# CAN_TO_USART_V2_2.net
KiCad netlist of a schematic drawn in Altium Designer
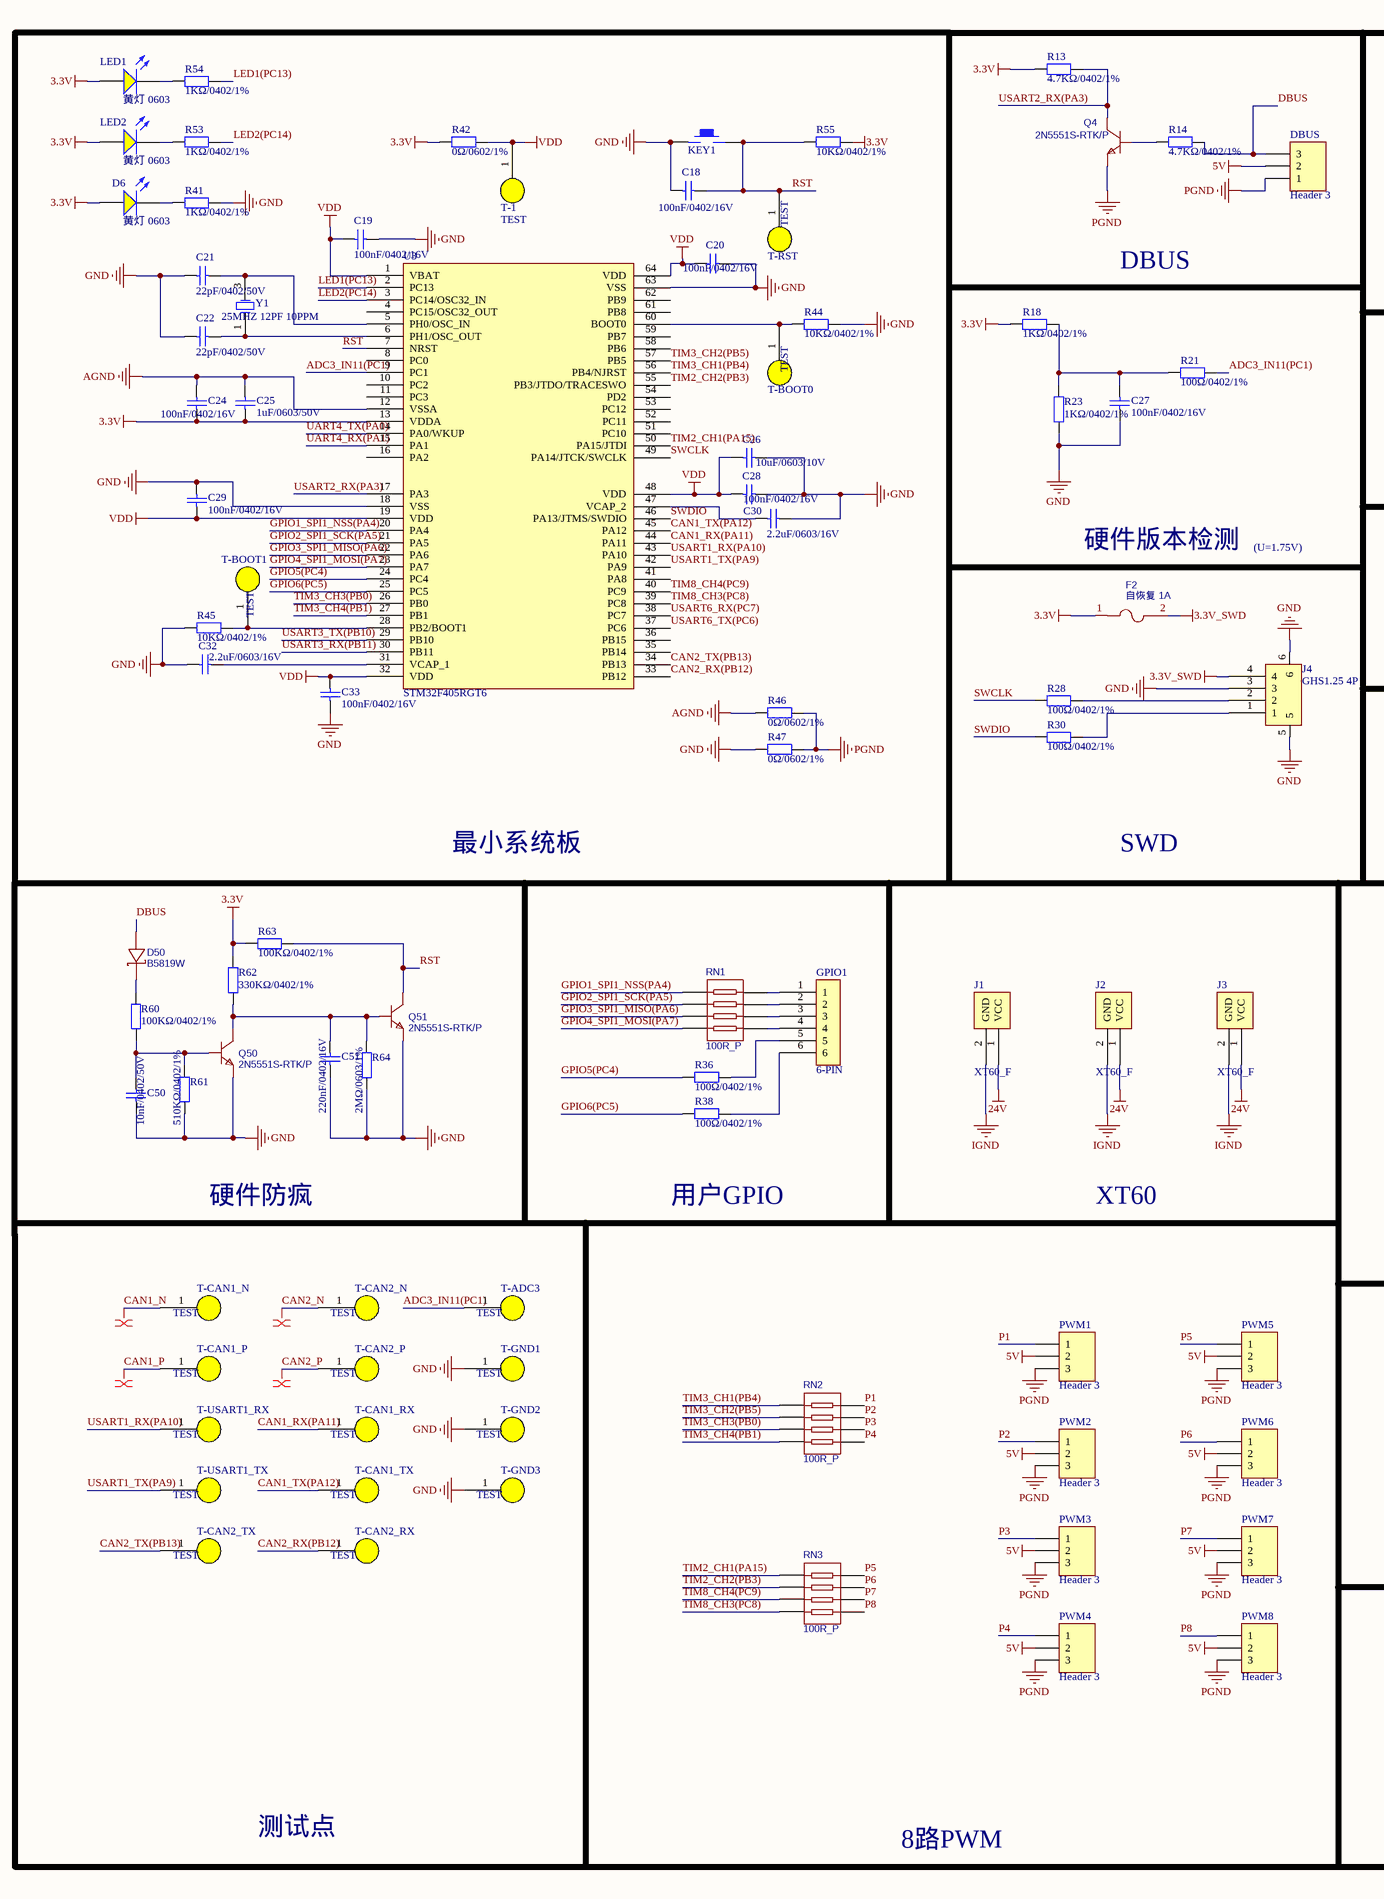
[diagram p0: CAN_TO_USART_V2.2.SchDoc, left]
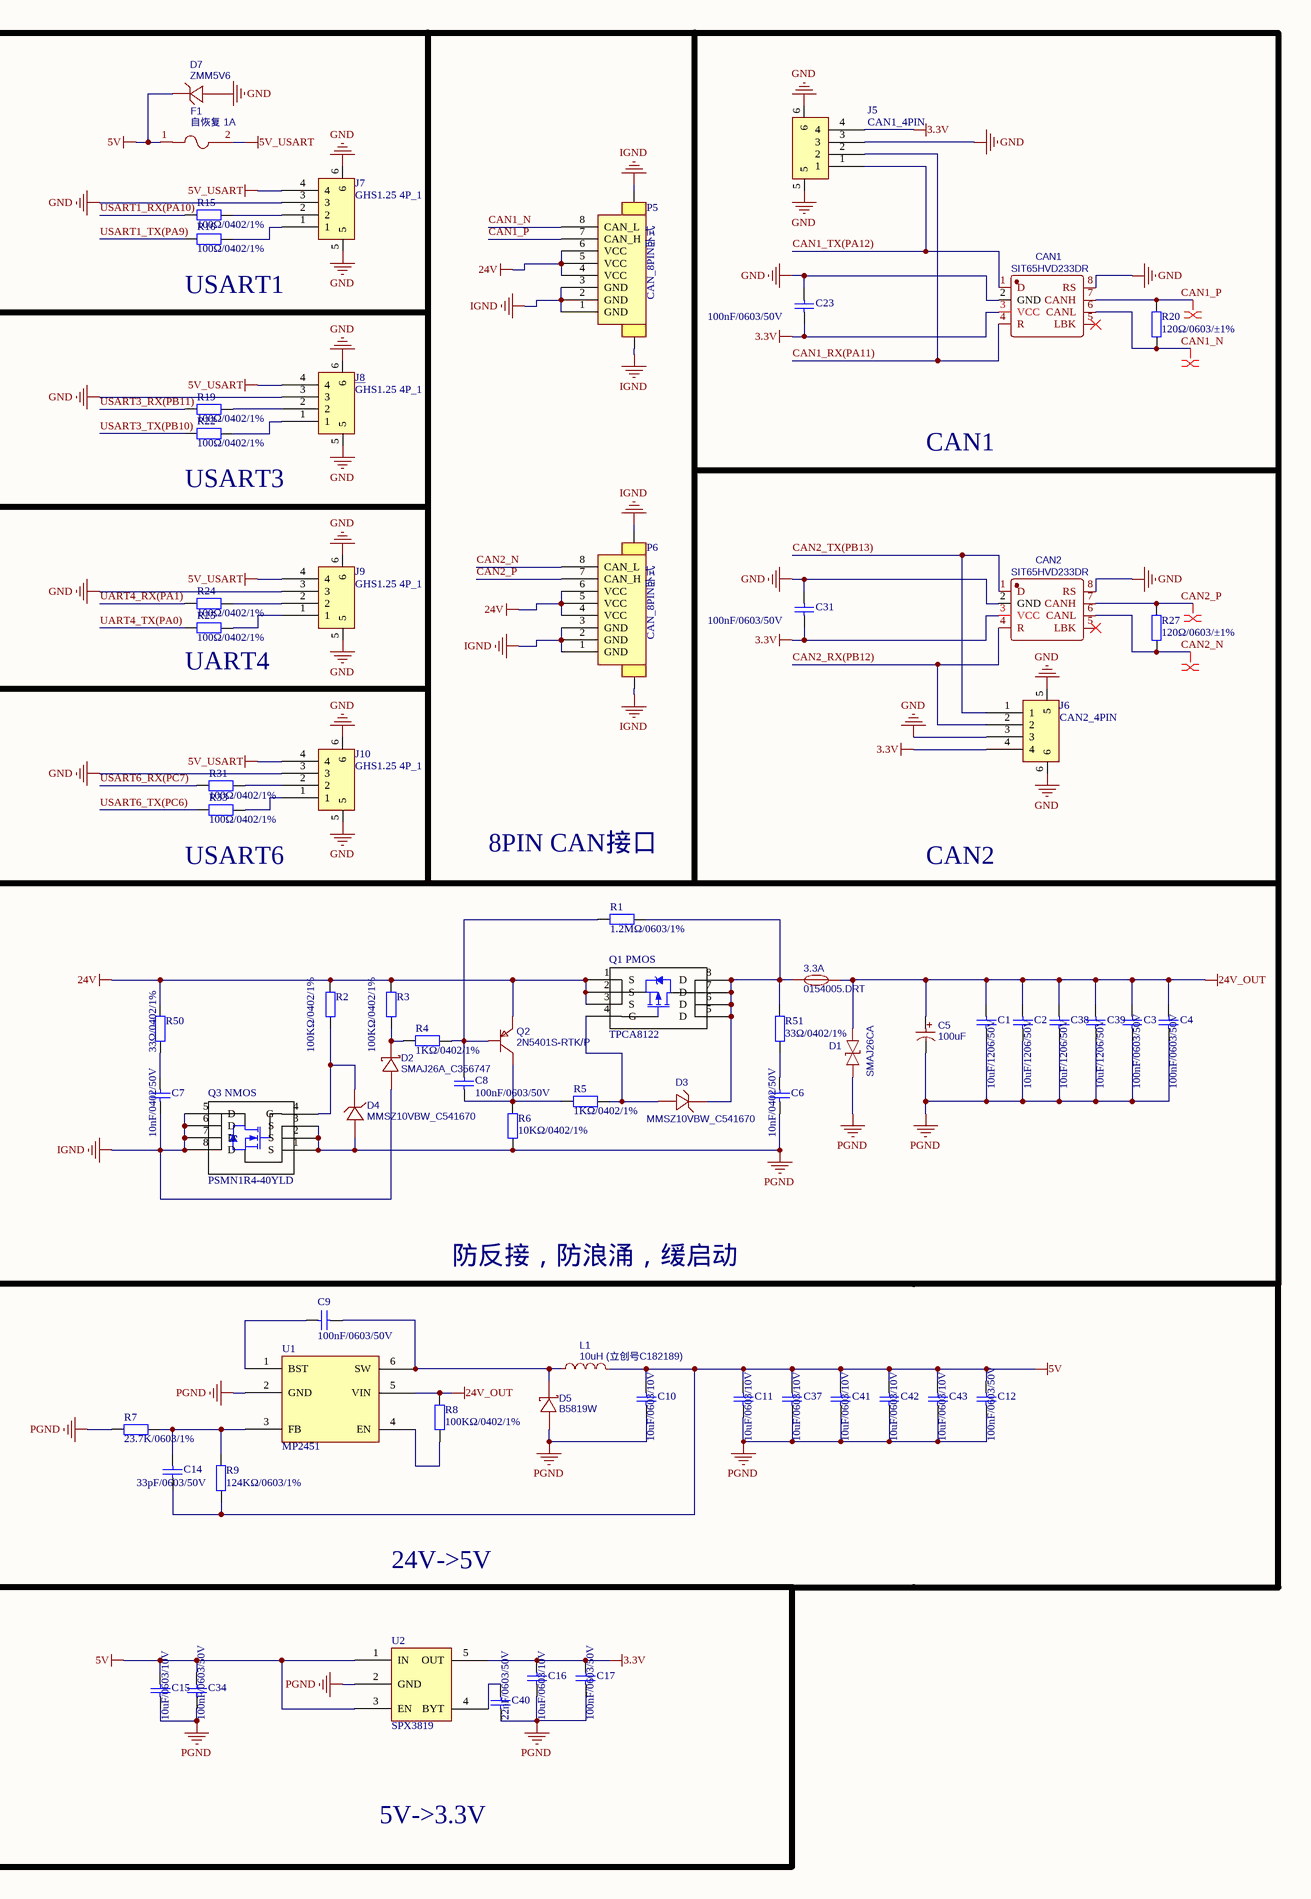
[diagram p1: CAN_TO_USART_V2.2.SchDoc, right]

(export (version "E")
  (design (tool "Eeschema 10.0.6"))
  (components
    (comp (ref "3.3A")
      (value "0154005.DRT")
      (footprint "FUSE 3.3A")
      (fields (field (name "BOM_SUPPLIER PART") "C206917") (field (name "CONTRIBUTOR") "LCSC"))
      (libsource (lib "altium-import") (part "root_0_mirrored_0154005.DRT_"))
    )
    (comp (ref "C1")
      (value "10uF/1206/50V")
      (footprint "1206_C")
      (description "贴片电容")
      (libsource (lib "Miscellaneous Devices LC") (part "1206 10uF (106) 10% 50V"))
    )
    (comp (ref "C2")
      (value "10uF/1206/50V")
      (footprint "1206_C")
      (description "贴片电容")
      (libsource (lib "Miscellaneous Devices LC") (part "1206 10uF (106) 10% 50V"))
    )
    (comp (ref "C3")
      (value "100nF/0603/50V")
      (footprint "0603_C")
      (description "贴片电容")
      (libsource (lib "Miscellaneous Devices LC") (part "0603 100nF (104) 10% 50V"))
    )
    (comp (ref "C4")
      (value "100nF/0603/50V")
      (footprint "0603_C")
      (description "贴片电容")
      (libsource (lib "Miscellaneous Devices LC") (part "0603 100nF (104) 10% 50V"))
    )
    (comp (ref "C5")
      (value "100uF")
      (footprint "100UF E")
      (fields
        (field (name "BOM_MANUFACTURER PART") "50V 100uF 8X12")
        (field (name "BOM_SUPPLIER PART") "C2749")
      )
      (libsource (lib "altium-import") (part "root_3_100uF_"))
    )
    (comp (ref "C6")
      (value "10nF/0402/50V")
      (footprint "0402_C")
      (description "贴片电容")
      (libsource (lib "Miscellaneous Devices LC") (part "0402 10nF (103) 10% 50V"))
    )
    (comp (ref "C7")
      (value "10nF/0402/50V")
      (footprint "0402_C")
      (description "贴片电容")
      (libsource (lib "Miscellaneous Devices LC") (part "0402 10nF (103) 10% 50V"))
    )
    (comp (ref "C8")
      (value "100nF/0603/50V")
      (footprint "0603_C")
      (description "贴片电容")
      (libsource (lib "Miscellaneous Devices LC") (part "0603 100nF (104) 10% 50V"))
    )
    (comp (ref "C9")
      (value "100nF/0603/50V")
      (footprint "0603_C")
      (description "贴片电容")
      (libsource (lib "Miscellaneous Devices LC") (part "0603 100nF (104) 10% 50V"))
    )
    (comp (ref "C10")
      (value "10uF/0603/10V")
      (footprint "0603_C")
      (description "贴片电容")
      (libsource (lib "Miscellaneous Devices LC") (part "0603 10uF (106) 10% 10V"))
    )
    (comp (ref "C11")
      (value "10uF/0603/10V")
      (footprint "0603_C")
      (description "贴片电容")
      (libsource (lib "Miscellaneous Devices LC") (part "0603 10uF (106) 10% 10V"))
    )
    (comp (ref "C12")
      (value "100nF/0603/50V")
      (footprint "0603_C")
      (description "贴片电容")
      (libsource (lib "Miscellaneous Devices LC") (part "0603 100nF (104) 10% 50V"))
    )
    (comp (ref "C14")
      (value "33pF/0603/50V")
      (footprint "0603_C")
      (description "贴片电容")
      (libsource (lib "Miscellaneous Devices LC") (part "0603 33pF (330) 5% 50V"))
    )
    (comp (ref "C15")
      (value "10uF/0603/10V")
      (footprint "0603_C")
      (description "贴片电容")
      (libsource (lib "Miscellaneous Devices LC") (part "0603 10uF (106) 10% 10V"))
    )
    (comp (ref "C16")
      (value "10uF/0603/10V")
      (footprint "0603_C")
      (description "贴片电容")
      (libsource (lib "Miscellaneous Devices LC") (part "0603 10uF (106) 10% 10V"))
    )
    (comp (ref "C17")
      (value "100nF/0603/50V")
      (footprint "0603_C")
      (description "贴片电容")
      (libsource (lib "Miscellaneous Devices LC") (part "0603 100nF (104) 10% 50V"))
    )
    (comp (ref "C18")
      (value "100nF/0402/16V")
      (footprint "0402_C")
      (description "贴片电容")
      (libsource (lib "Miscellaneous Devices LC") (part "0402 100nF (104) 10% 16V"))
    )
    (comp (ref "C19")
      (value "100nF/0402/16V")
      (footprint "0402_C")
      (description "贴片电容")
      (libsource (lib "Miscellaneous Devices LC") (part "0402 100nF (104) 10% 16V"))
    )
    (comp (ref "C20")
      (value "100nF/0402/16V")
      (footprint "0402_C")
      (description "贴片电容")
      (libsource (lib "Miscellaneous Devices LC") (part "0402 100nF (104) 10% 16V"))
    )
    (comp (ref "C21")
      (value "22pF/0402/50V")
      (footprint "0402_C")
      (description "贴片电容")
      (libsource (lib "Miscellaneous Devices LC") (part "0402 22pF (220) 5% 50V"))
    )
    (comp (ref "C22")
      (value "22pF/0402/50V")
      (footprint "0402_C")
      (description "贴片电容")
      (libsource (lib "Miscellaneous Devices LC") (part "0402 22pF (220) 5% 50V"))
    )
    (comp (ref "C23")
      (value "100nF/0603/50V")
      (footprint "0603_C")
      (description "贴片电容")
      (libsource (lib "Miscellaneous Devices LC") (part "0603 100nF (104) 10% 50V"))
    )
    (comp (ref "C24")
      (value "100nF/0402/16V")
      (footprint "0402_C")
      (description "贴片电容")
      (libsource (lib "Miscellaneous Devices LC") (part "0402 100nF (104) 10% 16V"))
    )
    (comp (ref "C25")
      (value "1uF/0603/50V")
      (footprint "0603_C")
      (description "贴片电容")
      (libsource (lib "Miscellaneous Devices LC") (part "0603 1uF (105) 10% 50V"))
    )
    (comp (ref "C26")
      (value "10uF/0603/10V")
      (footprint "0603_C")
      (description "贴片电容")
      (libsource (lib "Miscellaneous Devices LC") (part "0603 10uF (106) 10% 10V"))
    )
    (comp (ref "C27")
      (value "100nF/0402/16V")
      (footprint "0402_C")
      (description "贴片电容")
      (libsource (lib "Miscellaneous Devices LC") (part "0402 100nF (104) 10% 16V"))
    )
    (comp (ref "C28")
      (value "100nF/0402/16V")
      (footprint "0402_C")
      (description "贴片电容")
      (libsource (lib "Miscellaneous Devices LC") (part "0402 100nF (104) 10% 16V"))
    )
    (comp (ref "C29")
      (value "100nF/0402/16V")
      (footprint "0402_C")
      (description "贴片电容")
      (libsource (lib "Miscellaneous Devices LC") (part "0402 100nF (104) 10% 16V"))
    )
    (comp (ref "C30")
      (value "2.2uF/0603/16V")
      (footprint "0603_C")
      (description "贴片电容")
      (libsource (lib "Miscellaneous Devices LC") (part "0603 2.2uF (225) 10% 16V"))
    )
    (comp (ref "C31")
      (value "100nF/0603/50V")
      (footprint "0603_C")
      (description "贴片电容")
      (libsource (lib "Miscellaneous Devices LC") (part "0603 100nF (104) 10% 50V"))
    )
    (comp (ref "C32")
      (value "2.2uF/0603/16V")
      (footprint "0603_C")
      (description "贴片电容")
      (libsource (lib "Miscellaneous Devices LC") (part "0603 2.2uF (225) 10% 16V"))
    )
    (comp (ref "C33")
      (value "100nF/0402/16V")
      (footprint "0402_C")
      (description "贴片电容")
      (libsource (lib "Miscellaneous Devices LC") (part "0402 100nF (104) 10% 16V"))
    )
    (comp (ref "C34")
      (value "100nF/0603/50V")
      (footprint "0603_C")
      (description "贴片电容")
      (libsource (lib "Miscellaneous Devices LC") (part "0603 100nF (104) 10% 50V"))
    )
    (comp (ref "C37")
      (value "10uF/0603/10V")
      (footprint "0603_C")
      (description "贴片电容")
      (libsource (lib "Miscellaneous Devices LC") (part "0603 10uF (106) 10% 10V"))
    )
    (comp (ref "C38")
      (value "10uF/1206/50V")
      (footprint "1206_C")
      (description "贴片电容")
      (libsource (lib "Miscellaneous Devices LC") (part "1206 10uF (106) 10% 50V"))
    )
    (comp (ref "C39")
      (value "10uF/1206/50V")
      (footprint "1206_C")
      (description "贴片电容")
      (libsource (lib "Miscellaneous Devices LC") (part "1206 10uF (106) 10% 50V"))
    )
    (comp (ref "C40")
      (value "22nF/0603/50V")
      (footprint "0603_C")
      (description "贴片电容")
      (libsource (lib "Miscellaneous Devices LC") (part "0603 22nF (223) 10% 50V"))
    )
    (comp (ref "C41")
      (value "10uF/0603/10V")
      (footprint "0603_C")
      (description "贴片电容")
      (libsource (lib "Miscellaneous Devices LC") (part "0603 10uF (106) 10% 10V"))
    )
    (comp (ref "C42")
      (value "10uF/0603/10V")
      (footprint "0603_C")
      (description "贴片电容")
      (libsource (lib "Miscellaneous Devices LC") (part "0603 10uF (106) 10% 10V"))
    )
    (comp (ref "C43")
      (value "10uF/0603/10V")
      (footprint "0603_C")
      (description "贴片电容")
      (libsource (lib "Miscellaneous Devices LC") (part "0603 10uF (106) 10% 10V"))
    )
    (comp (ref "C50")
      (value "10nF/0402/50V")
      (footprint "0402_C")
      (description "贴片电容")
      (libsource (lib "Miscellaneous Devices LC") (part "0402 10nF (103) 10% 50V"))
    )
    (comp (ref "C51")
      (value "220nF/0402/16V")
      (footprint "0402_C")
      (description "贴片电容")
      (libsource (lib "Miscellaneous Devices LC") (part "0402 220nF (224) 10% 16V"))
    )
    (comp (ref "CAN1")
      (value "SIT65HVD233DR")
      (footprint "CAN-MCU")
      (fields (field (name "BOM_SUPPLIER PART") "C496620") (field (name "CONTRIBUTOR") "LCSC"))
      (libsource (lib "altium-import") (part "root_0_SIT65HVD233DR_"))
    )
    (comp (ref "CAN2")
      (value "SIT65HVD233DR")
      (footprint "CAN-MCU")
      (fields (field (name "BOM_SUPPLIER PART") "C496620") (field (name "CONTRIBUTOR") "LCSC"))
      (libsource (lib "altium-import") (part "root_0_SIT65HVD233DR_"))
    )
    (comp (ref "D1")
      (value "SMAJ26CA")
      (footprint "SMAJ26CA")
      (fields (field (name "BOM_SUPPLIER PART") "C353459") (field (name "CONTRIBUTOR") "LCSC"))
      (libsource (lib "altium-import") (part "root_1_SMAJ26CA_C353459_"))
    )
    (comp (ref "D2")
      (value "SMAJ26A_C356747")
      (footprint "SMA_L4.4-W2.8-LS5.4-RD")
      (fields
        (field (name "BOM_SUPPLIER PART") "C356747")
        (field (name "BOM_MANUFACTURER PART") "SMAJ26A")
        (field (name "CONTRIBUTOR") "LCSC")
      )
      (libsource (lib "altium-import") (part "root_3_SMAJ26A_C356747_"))
    )
    (comp (ref "D3")
      (value "MMSZ10VBW_C541670")
      (footprint "SOD-123_L2.7-W1.6-LS3.7-RD")
      (fields
        (field (name "BOM_SUPPLIER PART") "C541670")
        (field (name "BOM_MANUFACTURER PART") "MMSZ10VBW")
        (field (name "CONTRIBUTOR") "LCSC")
      )
      (libsource (lib "altium-import") (part "root_2_MMSZ10VBW_C541670_"))
    )
    (comp (ref "D4")
      (value "MMSZ10VBW_C541670")
      (footprint "SOD-123_L2.7-W1.6-LS3.7-RD")
      (fields
        (field (name "BOM_SUPPLIER PART") "C541670")
        (field (name "BOM_MANUFACTURER PART") "MMSZ10VBW")
        (field (name "CONTRIBUTOR") "LCSC")
      )
      (libsource (lib "altium-import") (part "root_3_MMSZ10VBW_C541670_"))
    )
    (comp (ref "D5")
      (value "B5819W")
      (footprint "SOD-123_L2.8-W1.8-LS3.7-RD")
      (fields (field (name "BOM_SUPPLIER PART") "C64885"))
      (libsource (lib "altium-import") (part "root_3_B5819W_"))
    )
    (comp (ref "D6")
      (value "黄灯 0603")
      (footprint "0603_LED_S1")
      (description "发光二极管")
      (libsource (lib "Miscellaneous Devices LC") (part "0603 黄灯"))
    )
    (comp (ref "D7")
      (value "ZMM5V6")
      (footprint "ZMM5.6V")
      (fields (field (name "BOM_SUPPLIER PART") "C8062"))
      (libsource (lib "altium-import") (part "root_0_ZMM5V6_"))
    )
    (comp (ref "D50")
      (value "B5819W")
      (footprint "SOD-123_L2.8-W1.8-LS3.7-RD")
      (fields (field (name "BOM_SUPPLIER PART") "C64885"))
      (libsource (lib "altium-import") (part "root_1_B5819W_"))
    )
    (comp (ref "DBUS")
      (value "Header 3")
      (footprint "HDR1X3")
      (description "Header, 3-Pin")
      (fields (field (name "PUBLISHER") "Altium Limited"))
      (libsource (lib "Miscellaneous Connectors") (part "Header 3"))
    )
    (comp (ref "F1")
      (value "自恢复 1A")
      (footprint "1A 0805")
      (fields
        (field (name "BOM_MANUFACTURER PART") "ASMD1206-100")
        (field (name "BOM_SUPPLIER PART") "C135340")
        (field (name "CONTRIBUTOR") "LCSC")
      )
      (libsource (lib "altium-import") (part "root_0_ASMD1206-100_"))
    )
    (comp (ref "F2")
      (value "自恢复 1A")
      (footprint "1A 0805")
      (fields
        (field (name "BOM_MANUFACTURER PART") "ASMD1206-100")
        (field (name "BOM_SUPPLIER PART") "C135340")
        (field (name "CONTRIBUTOR") "LCSC")
      )
      (libsource (lib "altium-import") (part "root_0_ASMD1206-100_"))
    )
    (comp (ref "GPIO1") (value "6-PIN") (footprint "6P") (libsource (lib "Chassis_Con") (part "6-PIN")))
    (comp (ref "J1")
      (value "XT60_F")
      (footprint "RobotLab_Common_Used:XT60_F（立式）")
      (libsource (lib "RobotLab_Common_Used") (part "XT60_F"))
    )
    (comp (ref "J2")
      (value "XT60_F")
      (footprint "RobotLab_Common_Used:XT60_F（立式）")
      (libsource (lib "RobotLab_Common_Used") (part "XT60_F"))
    )
    (comp (ref "J3")
      (value "XT60_F")
      (footprint "RobotLab_Common_Used:XT60_F（立式）")
      (libsource (lib "RobotLab_Common_Used") (part "XT60_F"))
    )
    (comp (ref "J4")
      (value "GHS1.25 4P")
      (footprint "RobotLab_Common_Used:SM04B-GHS立式")
      (description "立式")
      (libsource (lib "RobotLab_Common_Used") (part "GHS1.25 4P"))
    )
    (comp (ref "J5")
      (value "CAN1_4PIN")
      (footprint "RobotLab_Common_Used:SM04B-GHS卧式")
      (description "卧式短边")
      (libsource (lib "") (part "GHS1.25 4P_1_1"))
    )
    (comp (ref "J6")
      (value "CAN2_4PIN")
      (footprint "RobotLab_Common_Used:SM04B-GHS卧式")
      (description "卧式短边")
      (libsource (lib "") (part "GHS1.25 4P_1_2"))
    )
    (comp (ref "J7")
      (value "GHS1.25 4P_1")
      (footprint "RobotLab_Common_Used:SM04B-GHS卧式")
      (description "卧式短边")
      (libsource (lib "RobotLab_Common_Used") (part "GHS1.25 4P_1"))
    )
    (comp (ref "J8")
      (value "GHS1.25 4P_1")
      (footprint "RobotLab_Common_Used:SM04B-GHS卧式")
      (description "卧式短边")
      (libsource (lib "RobotLab_Common_Used") (part "GHS1.25 4P_1"))
    )
    (comp (ref "J9")
      (value "GHS1.25 4P_1")
      (footprint "RobotLab_Common_Used:SM04B-GHS卧式")
      (description "卧式短边")
      (libsource (lib "RobotLab_Common_Used") (part "GHS1.25 4P_1"))
    )
    (comp (ref "J10")
      (value "GHS1.25 4P_1")
      (footprint "RobotLab_Common_Used:SM04B-GHS卧式")
      (description "卧式短边")
      (libsource (lib "RobotLab_Common_Used") (part "GHS1.25 4P_1"))
    )
    (comp (ref "KEY1") (value "KEY_M") (footprint "KEY") (libsource (lib "MiniSTM32 V3.0封装库") (part "KEY_M")))
    (comp (ref "L1")
      (value "10uH (立创号C182189)")
      (footprint "10UH 1A")
      (fields
        (field (name "BOM_SUPPLIER PART") "C182189")
        (field (name "BOM_MANUFACTURER PART") "SLW5040S100MST")
        (field (name "CONTRIBUTOR") "LCSC")
      )
      (libsource (lib "altium-import") (part "root_0_10uH_"))
    )
    (comp (ref "LED1")
      (value "黄灯 0603")
      (footprint "0603_LED_S1")
      (description "发光二极管")
      (libsource (lib "Miscellaneous Devices LC") (part "0603 黄灯"))
    )
    (comp (ref "LED2")
      (value "黄灯 0603")
      (footprint "0603_LED_S1")
      (description "发光二极管")
      (libsource (lib "Miscellaneous Devices LC") (part "0603 黄灯"))
    )
    (comp (ref "P5")
      (value "CAN_8PIN卧式")
      (footprint "RobotLab_Common_Used:8Pin")
      (description "卧式")
      (libsource (lib "RobotLab_Common_Used") (part "CAN_8PIN"))
    )
    (comp (ref "P6")
      (value "CAN_8PIN卧式")
      (footprint "RobotLab_Common_Used:8Pin")
      (description "卧式")
      (libsource (lib "RobotLab_Common_Used") (part "CAN_8PIN"))
    )
    (comp (ref "PWM1")
      (value "Header 3")
      (footprint "HDR1X3")
      (description "Header, 3-Pin")
      (fields (field (name "PUBLISHER") "Altium Limited"))
      (libsource (lib "") (part "Header 3_1"))
    )
    (comp (ref "PWM2")
      (value "Header 3")
      (footprint "HDR1X3")
      (description "Header, 3-Pin")
      (fields (field (name "PUBLISHER") "Altium Limited"))
      (libsource (lib "") (part "Header 3_1"))
    )
    (comp (ref "PWM3")
      (value "Header 3")
      (footprint "HDR1X3")
      (description "Header, 3-Pin")
      (fields (field (name "PUBLISHER") "Altium Limited"))
      (libsource (lib "") (part "Header 3_1"))
    )
    (comp (ref "PWM4")
      (value "Header 3")
      (footprint "HDR1X3")
      (description "Header, 3-Pin")
      (fields (field (name "PUBLISHER") "Altium Limited"))
      (libsource (lib "") (part "Header 3_1"))
    )
    (comp (ref "PWM5")
      (value "Header 3")
      (footprint "HDR1X3")
      (description "Header, 3-Pin")
      (fields (field (name "PUBLISHER") "Altium Limited"))
      (libsource (lib "") (part "Header 3_1"))
    )
    (comp (ref "PWM6")
      (value "Header 3")
      (footprint "HDR1X3")
      (description "Header, 3-Pin")
      (fields (field (name "PUBLISHER") "Altium Limited"))
      (libsource (lib "") (part "Header 3_1"))
    )
    (comp (ref "PWM7")
      (value "Header 3")
      (footprint "HDR1X3")
      (description "Header, 3-Pin")
      (fields (field (name "PUBLISHER") "Altium Limited"))
      (libsource (lib "") (part "Header 3_1"))
    )
    (comp (ref "PWM8")
      (value "Header 3")
      (footprint "HDR1X3")
      (description "Header, 3-Pin")
      (fields (field (name "PUBLISHER") "Altium Limited"))
      (libsource (lib "") (part "Header 3_1"))
    )
    (comp (ref "Q1 PMOS")
      (value "TPCA8122")
      (footprint "PMOS TCPA8122")
      (fields (field (name "PUBLISHER") "Altium Limited"))
      (libsource (lib "CAN_TO_USART") (part "PMOS 8PIN"))
    )
    (comp (ref "Q2")
      (value "2N5401S-RTK/P")
      (footprint "SOT-23-3_L2.9-W1.6-P1.90-LS2.8-TR-CW")
      (fields (field (name "BOM_SUPPLIER PART") "C147293") (field (name "CONTRIBUTOR") "LCSC"))
      (libsource (lib "altium-import") (part "root_2_mirrored_2N5401S-RTK/P_"))
    )
    (comp (ref "Q3 NMOS")
      (value "PSMN1R4-40YLD")
      (footprint "NMOS PSMN1R5-30")
      (fields (field (name "PUBLISHER") "Altium Limited"))
      (libsource (lib "CAN_TO_USART") (part "NMOS 8PIN"))
    )
    (comp (ref "Q4")
      (value "2N5551S-RTK/P")
      (footprint "2N5551")
      (fields (field (name "BOM_SUPPLIER PART") "C112669") (field (name "CONTRIBUTOR") "LCSC"))
      (libsource (lib "altium-import") (part "root_0_mirrored_2N5551S-RTK/P_"))
    )
    (comp (ref "Q50")
      (value "2N5551S-RTK/P")
      (footprint "2N5551")
      (fields (field (name "BOM_SUPPLIER PART") "C112669") (field (name "CONTRIBUTOR") "LCSC"))
      (libsource (lib "altium-import") (part "root_0_2N5551S-RTK/P_"))
    )
    (comp (ref "Q51")
      (value "2N5551S-RTK/P")
      (footprint "2N5551")
      (fields (field (name "BOM_SUPPLIER PART") "C112669") (field (name "CONTRIBUTOR") "LCSC"))
      (libsource (lib "altium-import") (part "root_0_2N5551S-RTK/P_"))
    )
    (comp (ref "R1")
      (value "1.2MΩ/0603/1%")
      (footprint "0603_R")
      (description "贴片电阻")
      (libsource (lib "Miscellaneous Devices LC") (part "0603 1.2MΩ (1204) 1%"))
    )
    (comp (ref "R2")
      (value "100KΩ/0402/1%")
      (footprint "0402_R")
      (description "贴片电阻")
      (libsource (lib "Miscellaneous Devices LC") (part "0402 100KΩ (1003) 1%"))
    )
    (comp (ref "R3")
      (value "100KΩ/0402/1%")
      (footprint "0402_R")
      (description "贴片电阻")
      (libsource (lib "Miscellaneous Devices LC") (part "0402 100KΩ (1003) 1%"))
    )
    (comp (ref "R4")
      (value "1KΩ/0402/1%")
      (footprint "0402_R")
      (description "贴片电阻")
      (libsource (lib "Miscellaneous Devices LC") (part "0402 1KΩ (1001) 1%"))
    )
    (comp (ref "R5")
      (value "1KΩ/0402/1%")
      (footprint "0402_R")
      (description "贴片电阻")
      (libsource (lib "Miscellaneous Devices LC") (part "0402 1KΩ (1001) 1%"))
    )
    (comp (ref "R6")
      (value "10KΩ/0402/1%")
      (footprint "0402_R")
      (description "贴片电阻")
      (libsource (lib "") (part "0402 10KΩ (1002) 1%_1"))
    )
    (comp (ref "R7")
      (value "23.7K/0603/1%")
      (footprint "0603_R")
      (description "贴片电阻")
      (libsource (lib "") (part "0603 3KΩ (3001) 1%_1"))
    )
    (comp (ref "R8")
      (value "100KΩ/0402/1%")
      (footprint "0402_R")
      (description "贴片电阻")
      (libsource (lib "Miscellaneous Devices LC") (part "0402 100KΩ (1003) 1%"))
    )
    (comp (ref "R9")
      (value "124KΩ/0603/1%")
      (footprint "0603_R")
      (description "贴片电阻")
      (libsource (lib "Miscellaneous Devices LC") (part "0603 3KΩ (3001) 1%"))
    )
    (comp (ref "R13")
      (value "4.7KΩ/0402/1%")
      (footprint "0402_R")
      (description "贴片电阻")
      (libsource (lib "Miscellaneous Devices LC") (part "0402 4.7KΩ (4701) 1%"))
    )
    (comp (ref "R14")
      (value "4.7KΩ/0402/1%")
      (footprint "0402_R")
      (description "贴片电阻")
      (libsource (lib "Miscellaneous Devices LC") (part "0402 4.7KΩ (4701) 1%"))
    )
    (comp (ref "R15")
      (value "100Ω/0402/1%")
      (footprint "0402_R")
      (description "贴片电阻")
      (libsource (lib "Miscellaneous Devices LC") (part "0402 100Ω (1000) 1%"))
    )
    (comp (ref "R16")
      (value "100Ω/0402/1%")
      (footprint "0402_R")
      (description "贴片电阻")
      (libsource (lib "Miscellaneous Devices LC") (part "0402 100Ω (1000) 1%"))
    )
    (comp (ref "R18")
      (value "1KΩ/0402/1%")
      (footprint "0402_R")
      (description "贴片电阻")
      (libsource (lib "Miscellaneous Devices LC") (part "0402 1KΩ (1001) 1%"))
    )
    (comp (ref "R19")
      (value "100Ω/0402/1%")
      (footprint "0402_R")
      (description "贴片电阻")
      (libsource (lib "Miscellaneous Devices LC") (part "0402 100Ω (1000) 1%"))
    )
    (comp (ref "R20")
      (value "120Ω/0603/±1%")
      (footprint "0603_R")
      (description "贴片电阻")
      (libsource (lib "Miscellaneous Devices LC") (part "0603 120Ω (1200) 1%"))
    )
    (comp (ref "R21")
      (value "100Ω/0402/1%")
      (footprint "0402_R")
      (description "贴片电阻")
      (libsource (lib "Miscellaneous Devices LC") (part "0402 100Ω (1000) 1%"))
    )
    (comp (ref "R22")
      (value "100Ω/0402/1%")
      (footprint "0402_R")
      (description "贴片电阻")
      (libsource (lib "Miscellaneous Devices LC") (part "0402 100Ω (1000) 1%"))
    )
    (comp (ref "R23")
      (value "1KΩ/0402/1%")
      (footprint "0402_R")
      (description "贴片电阻")
      (libsource (lib "") (part "0402 1KΩ (1001) 1%_1"))
    )
    (comp (ref "R24")
      (value "100Ω/0402/1%")
      (footprint "0402_R")
      (description "贴片电阻")
      (libsource (lib "Miscellaneous Devices LC") (part "0402 100Ω (1000) 1%"))
    )
    (comp (ref "R25")
      (value "100Ω/0402/1%")
      (footprint "0402_R")
      (description "贴片电阻")
      (libsource (lib "Miscellaneous Devices LC") (part "0402 100Ω (1000) 1%"))
    )
    (comp (ref "R27")
      (value "120Ω/0603/±1%")
      (footprint "0603_R")
      (description "贴片电阻")
      (libsource (lib "Miscellaneous Devices LC") (part "0603 120Ω (1200) 1%"))
    )
    (comp (ref "R28")
      (value "100Ω/0402/1%")
      (footprint "0402_R")
      (description "贴片电阻")
      (libsource (lib "Miscellaneous Devices LC") (part "0402 100Ω (1000) 1%"))
    )
    (comp (ref "R30")
      (value "100Ω/0402/1%")
      (footprint "0402_R")
      (description "贴片电阻")
      (libsource (lib "Miscellaneous Devices LC") (part "0402 100Ω (1000) 1%"))
    )
    (comp (ref "R31")
      (value "100Ω/0402/1%")
      (footprint "0402_R")
      (description "贴片电阻")
      (libsource (lib "Miscellaneous Devices LC") (part "0402 100Ω (1000) 1%"))
    )
    (comp (ref "R33")
      (value "100Ω/0402/1%")
      (footprint "0402_R")
      (description "贴片电阻")
      (libsource (lib "Miscellaneous Devices LC") (part "0402 100Ω (1000) 1%"))
    )
    (comp (ref "R36")
      (value "100Ω/0402/1%")
      (footprint "0402_R")
      (description "贴片电阻")
      (libsource (lib "Miscellaneous Devices LC") (part "0402 100Ω (1000) 1%"))
    )
    (comp (ref "R38")
      (value "100Ω/0402/1%")
      (footprint "0402_R")
      (description "贴片电阻")
      (libsource (lib "Miscellaneous Devices LC") (part "0402 100Ω (1000) 1%"))
    )
    (comp (ref "R41")
      (value "1KΩ/0402/1%")
      (footprint "0402_R")
      (description "贴片电阻")
      (libsource (lib "Miscellaneous Devices LC") (part "0402 1KΩ (1001) 1%"))
    )
    (comp (ref "R42")
      (value "0Ω/0602/1%")
      (footprint "0603_R")
      (description "贴片电阻")
      (libsource (lib "Miscellaneous Devices LC") (part "0603 0Ω (0R0) 1%"))
    )
    (comp (ref "R44")
      (value "10KΩ/0402/1%")
      (footprint "0402_R")
      (description "贴片电阻")
      (libsource (lib "Miscellaneous Devices LC") (part "0402 10KΩ (1002) 1%"))
    )
    (comp (ref "R45")
      (value "10KΩ/0402/1%")
      (footprint "0402_R")
      (description "贴片电阻")
      (libsource (lib "Miscellaneous Devices LC") (part "0402 10KΩ (1002) 1%"))
    )
    (comp (ref "R46")
      (value "0Ω/0602/1%")
      (footprint "0603_R")
      (description "贴片电阻")
      (libsource (lib "Miscellaneous Devices LC") (part "0603 0Ω (0R0) 1%"))
    )
    (comp (ref "R47")
      (value "0Ω/0602/1%")
      (footprint "0603_R")
      (description "贴片电阻")
      (libsource (lib "Miscellaneous Devices LC") (part "0603 0Ω (0R0) 1%"))
    )
    (comp (ref "R50")
      (value "33Ω/0402/1%")
      (footprint "0402_R")
      (description "贴片电阻")
      (libsource (lib "Miscellaneous Devices LC") (part "0402 33Ω (33R0) 1%"))
    )
    (comp (ref "R51")
      (value "33Ω/0402/1%")
      (footprint "0402_R")
      (description "贴片电阻")
      (libsource (lib "Miscellaneous Devices LC") (part "0402 33Ω (33R0) 1%"))
    )
    (comp (ref "R53")
      (value "1KΩ/0402/1%")
      (footprint "0402_R")
      (description "贴片电阻")
      (libsource (lib "Miscellaneous Devices LC") (part "0402 1KΩ (1001) 1%"))
    )
    (comp (ref "R54")
      (value "1KΩ/0402/1%")
      (footprint "0402_R")
      (description "贴片电阻")
      (libsource (lib "Miscellaneous Devices LC") (part "0402 1KΩ (1001) 1%"))
    )
    (comp (ref "R55")
      (value "10KΩ/0402/1%")
      (footprint "0402_R")
      (description "贴片电阻")
      (libsource (lib "Miscellaneous Devices LC") (part "0402 10KΩ (1002) 1%"))
    )
    (comp (ref "R60")
      (value "100KΩ/0402/1%")
      (footprint "0402_R")
      (description "贴片电阻")
      (libsource (lib "") (part "0402 100KΩ (1003) 1%_2"))
    )
    (comp (ref "R61")
      (value "510KΩ/0402/1%")
      (footprint "0402_R")
      (description "贴片电阻")
      (libsource (lib "Miscellaneous Devices LC") (part "0402 510KΩ (5103) 1%"))
    )
    (comp (ref "R62")
      (value "330KΩ/0402/1%")
      (footprint "0402_R")
      (description "贴片电阻")
      (libsource (lib "Miscellaneous Devices LC") (part "0402 330KΩ (3303) 1%"))
    )
    (comp (ref "R63")
      (value "100KΩ/0402/1%")
      (footprint "0402_R")
      (description "贴片电阻")
      (libsource (lib "") (part "0402 100KΩ (1003) 1%_1"))
    )
    (comp (ref "R64")
      (value "2MΩ/0603/1%")
      (footprint "0603_R")
      (description "贴片电阻")
      (libsource (lib "Miscellaneous Devices LC") (part "0603 2MΩ (2004) 1%"))
    )
    (comp (ref "RN1")
      (value "100R_P")
      (footprint "100R_P")
      (fields
        (field (name "BOM_MANUFACTURER PART") "4D03WGJ0101T5E")
        (field (name "BOM_SUPPLIER PART") "C25506")
      )
      (libsource (lib "CAN_TO_USART") (part "100R_P"))
    )
    (comp (ref "RN2")
      (value "100R_P")
      (footprint "100R_P")
      (fields
        (field (name "BOM_MANUFACTURER PART") "4D03WGJ0101T5E")
        (field (name "BOM_SUPPLIER PART") "C25506")
      )
      (libsource (lib "CAN_TO_USART") (part "100R_P"))
    )
    (comp (ref "RN3")
      (value "100R_P")
      (footprint "100R_P")
      (fields
        (field (name "BOM_MANUFACTURER PART") "4D03WGJ0101T5E")
        (field (name "BOM_SUPPLIER PART") "C25506")
      )
      (libsource (lib "CAN_TO_USART") (part "100R_P"))
    )
    (comp (ref "T-1") (value "TEST") (footprint "TEST-POINT") (libsource (lib "CAN_TO_USART") (part "TEST")))
    (comp (ref "T-ADC3")
      (value "TEST")
      (footprint "TEST-POINT")
      (libsource (lib "CAN_TO_USART") (part "TEST"))
    )
    (comp (ref "T-BOOT0")
      (value "TEST")
      (footprint "TEST-POINT")
      (libsource (lib "CAN_TO_USART") (part "TEST"))
    )
    (comp (ref "T-BOOT1")
      (value "TEST")
      (footprint "TEST-POINT")
      (libsource (lib "CAN_TO_USART") (part "TEST"))
    )
    (comp (ref "T-CAN1_N")
      (value "TEST")
      (footprint "TEST-POINT")
      (libsource (lib "CAN_TO_USART") (part "TEST"))
    )
    (comp (ref "T-CAN1_P")
      (value "TEST")
      (footprint "TEST-POINT")
      (libsource (lib "CAN_TO_USART") (part "TEST"))
    )
    (comp (ref "T-CAN1_RX")
      (value "TEST")
      (footprint "TEST-POINT")
      (libsource (lib "CAN_TO_USART") (part "TEST"))
    )
    (comp (ref "T-CAN1_TX")
      (value "TEST")
      (footprint "TEST-POINT")
      (libsource (lib "CAN_TO_USART") (part "TEST"))
    )
    (comp (ref "T-CAN2_N")
      (value "TEST")
      (footprint "TEST-POINT")
      (libsource (lib "CAN_TO_USART") (part "TEST"))
    )
    (comp (ref "T-CAN2_P")
      (value "TEST")
      (footprint "TEST-POINT")
      (libsource (lib "CAN_TO_USART") (part "TEST"))
    )
    (comp (ref "T-CAN2_RX")
      (value "TEST")
      (footprint "TEST-POINT")
      (libsource (lib "CAN_TO_USART") (part "TEST"))
    )
    (comp (ref "T-CAN2_TX")
      (value "TEST")
      (footprint "TEST-POINT")
      (libsource (lib "CAN_TO_USART") (part "TEST"))
    )
    (comp (ref "T-GND1")
      (value "TEST")
      (footprint "TEST-POINT")
      (libsource (lib "CAN_TO_USART") (part "TEST"))
    )
    (comp (ref "T-GND2")
      (value "TEST")
      (footprint "TEST-POINT")
      (libsource (lib "CAN_TO_USART") (part "TEST"))
    )
    (comp (ref "T-GND3")
      (value "TEST")
      (footprint "TEST-POINT")
      (libsource (lib "CAN_TO_USART") (part "TEST"))
    )
    (comp (ref "T-RST")
      (value "TEST")
      (footprint "TEST-POINT")
      (libsource (lib "CAN_TO_USART") (part "TEST"))
    )
    (comp (ref "T-USART1_RX")
      (value "TEST")
      (footprint "TEST-POINT")
      (libsource (lib "CAN_TO_USART") (part "TEST"))
    )
    (comp (ref "T-USART1_TX")
      (value "TEST")
      (footprint "TEST-POINT")
      (libsource (lib "CAN_TO_USART") (part "TEST"))
    )
    (comp (ref "U1") (value "MP2451") (footprint "MP2451") (libsource (lib "CAN_TO_USART") (part "MP2451")))
    (comp (ref "U2")
      (value "SPX3819")
      (footprint "SPX3819")
      (libsource (lib "CAN_TO_USART") (part "SPX3819"))
    )
    (comp (ref "U3")
      (value "STM32F405RGT6")
      (footprint "STM32F405RGT6")
      (libsource (lib "Chassis_Con") (part "STM32F405RGT6"))
    )
    (comp (ref "Y1")
      (value "25MHZ 12PF 10PPM")
      (footprint "SMD-3225_4P")
      (description "贴片晶振")
      (libsource (lib "Miscellaneous Devices LC") (part "SMD-3225_4P  25MHZ 12PF 10PPM"))
    )
  )
  (nets
    (net (code "1") (name "/ADC3_IN11(PC1)") (class "Default")
      (node (ref "R21") (pin "2") (pinfunction "2_2") (pintype "passive"))
      (node (ref "T-ADC3") (pin "1") (pintype "passive"))
      (node (ref "U3") (pin "9") (pinfunction "PC1_9") (pintype "passive"))
    )
    (net (code "2") (name "/CAN1_N") (class "Default")
      (node (ref "CAN1") (pin "6") (pinfunction "CANL_6") (pintype "passive"))
      (node (ref "P5") (pin "8") (pinfunction "CAN_L_8") (pintype "passive"))
      (node (ref "R20") (pin "1") (pinfunction "1_1") (pintype "passive"))
      (node (ref "T-CAN1_N") (pin "1") (pintype "passive"))
    )
    (net (code "3") (name "/CAN1_P") (class "Default")
      (node (ref "CAN1") (pin "7") (pinfunction "CANH_7") (pintype "passive"))
      (node (ref "P5") (pin "7") (pinfunction "CAN_H_7") (pintype "passive"))
      (node (ref "R20") (pin "2") (pinfunction "2_2") (pintype "passive"))
      (node (ref "T-CAN1_P") (pin "1") (pintype "passive"))
    )
    (net (code "4") (name "/CAN1_RX(PA11)") (class "Default")
      (node (ref "CAN1") (pin "4") (pinfunction "R_4") (pintype "passive"))
      (node (ref "J5") (pin "2") (pinfunction "2_2") (pintype "passive"))
      (node (ref "T-CAN1_RX") (pin "1") (pintype "passive"))
      (node (ref "U3") (pin "44") (pinfunction "PA11_44") (pintype "passive"))
    )
    (net (code "5") (name "/CAN1_TX(PA12)") (class "Default")
      (node (ref "CAN1") (pin "1") (pinfunction "D_1") (pintype "passive"))
      (node (ref "J5") (pin "1") (pinfunction "1_1") (pintype "passive"))
      (node (ref "T-CAN1_TX") (pin "1") (pintype "passive"))
      (node (ref "U3") (pin "45") (pinfunction "PA12_45") (pintype "passive"))
    )
    (net (code "6") (name "/CAN2_N") (class "Default")
      (node (ref "CAN2") (pin "6") (pinfunction "CANL_6") (pintype "passive"))
      (node (ref "P6") (pin "8") (pinfunction "CAN_L_8") (pintype "passive"))
      (node (ref "R27") (pin "1") (pinfunction "1_1") (pintype "passive"))
      (node (ref "T-CAN2_N") (pin "1") (pintype "passive"))
    )
    (net (code "7") (name "/CAN2_P") (class "Default")
      (node (ref "CAN2") (pin "7") (pinfunction "CANH_7") (pintype "passive"))
      (node (ref "P6") (pin "7") (pinfunction "CAN_H_7") (pintype "passive"))
      (node (ref "R27") (pin "2") (pinfunction "2_2") (pintype "passive"))
      (node (ref "T-CAN2_P") (pin "1") (pintype "passive"))
    )
    (net (code "8") (name "/CAN2_RX(PB12)") (class "Default")
      (node (ref "CAN2") (pin "4") (pinfunction "R_4") (pintype "passive"))
      (node (ref "J6") (pin "2") (pinfunction "2_2") (pintype "passive"))
      (node (ref "T-CAN2_RX") (pin "1") (pintype "passive"))
      (node (ref "U3") (pin "33") (pinfunction "PB12_33") (pintype "passive"))
    )
    (net (code "9") (name "/CAN2_TX(PB13)") (class "Default")
      (node (ref "CAN2") (pin "1") (pinfunction "D_1") (pintype "passive"))
      (node (ref "J6") (pin "1") (pinfunction "1_1") (pintype "passive"))
      (node (ref "T-CAN2_TX") (pin "1") (pintype "passive"))
      (node (ref "U3") (pin "34") (pinfunction "PB13_34") (pintype "passive"))
    )
    (net (code "10") (name "/DBUS") (class "Default")
      (node (ref "D50") (pin "2") (pinfunction "A_2") (pintype "passive"))
      (node (ref "DBUS") (pin "3") (pinfunction "3_3") (pintype "passive"))
      (node (ref "R14") (pin "2") (pinfunction "2_2") (pintype "passive"))
    )
    (net (code "11") (name "/GPIO1_SPI1_NSS(PA4)") (class "Default")
      (node (ref "RN1") (pin "8") (pinfunction "8_8") (pintype "passive"))
      (node (ref "U3") (pin "20") (pinfunction "PA4_20") (pintype "passive"))
    )
    (net (code "12") (name "/GPIO2_SPI1_SCK(PA5)") (class "Default")
      (node (ref "RN1") (pin "7") (pinfunction "7_7") (pintype "passive"))
      (node (ref "U3") (pin "21") (pinfunction "PA5_21") (pintype "passive"))
    )
    (net (code "13") (name "/GPIO3_SPI1_MISO(PA6)") (class "Default")
      (node (ref "RN1") (pin "6") (pinfunction "6_6") (pintype "passive"))
      (node (ref "U3") (pin "22") (pinfunction "PA6_22") (pintype "passive"))
    )
    (net (code "14") (name "/GPIO4_SPI1_MOSI(PA7)") (class "Default")
      (node (ref "RN1") (pin "5") (pinfunction "5_5") (pintype "passive"))
      (node (ref "U3") (pin "23") (pinfunction "PA7_23") (pintype "passive"))
    )
    (net (code "15") (name "/GPIO5(PC4)") (class "Default")
      (node (ref "R36") (pin "1") (pinfunction "1_1") (pintype "passive"))
      (node (ref "U3") (pin "24") (pinfunction "PC4_24") (pintype "passive"))
    )
    (net (code "16") (name "/GPIO6(PC5)") (class "Default")
      (node (ref "R38") (pin "1") (pinfunction "1_1") (pintype "passive"))
      (node (ref "U3") (pin "25") (pinfunction "PC5_25") (pintype "passive"))
    )
    (net (code "17") (name "/LED1(PC13)") (class "Default")
      (node (ref "R54") (pin "2") (pinfunction "2_2") (pintype "passive"))
      (node (ref "U3") (pin "2") (pinfunction "PC13_2") (pintype "passive"))
    )
    (net (code "18") (name "/LED2(PC14)") (class "Default")
      (node (ref "R53") (pin "2") (pinfunction "2_2") (pintype "passive"))
      (node (ref "U3") (pin "3") (pinfunction "PC14/OSC32_IN_3") (pintype "passive"))
    )
    (net (code "19") (name "/P1") (class "Default")
      (node (ref "PWM1") (pin "1") (pinfunction "1_1") (pintype "passive"))
      (node (ref "RN2") (pin "8") (pinfunction "8_8") (pintype "passive"))
    )
    (net (code "20") (name "/P2") (class "Default")
      (node (ref "PWM2") (pin "1") (pinfunction "1_1") (pintype "passive"))
      (node (ref "RN2") (pin "7") (pinfunction "7_7") (pintype "passive"))
    )
    (net (code "21") (name "/P3") (class "Default")
      (node (ref "PWM3") (pin "1") (pinfunction "1_1") (pintype "passive"))
      (node (ref "RN2") (pin "6") (pinfunction "6_6") (pintype "passive"))
    )
    (net (code "22") (name "/P4") (class "Default")
      (node (ref "PWM4") (pin "1") (pinfunction "1_1") (pintype "passive"))
      (node (ref "RN2") (pin "5") (pinfunction "5_5") (pintype "passive"))
    )
    (net (code "23") (name "/P5") (class "Default")
      (node (ref "PWM5") (pin "1") (pinfunction "1_1") (pintype "passive"))
      (node (ref "RN3") (pin "8") (pinfunction "8_8") (pintype "passive"))
    )
    (net (code "24") (name "/P6") (class "Default")
      (node (ref "PWM6") (pin "1") (pinfunction "1_1") (pintype "passive"))
      (node (ref "RN3") (pin "7") (pinfunction "7_7") (pintype "passive"))
    )
    (net (code "25") (name "/P7") (class "Default")
      (node (ref "PWM7") (pin "1") (pinfunction "1_1") (pintype "passive"))
      (node (ref "RN3") (pin "6") (pinfunction "6_6") (pintype "passive"))
    )
    (net (code "26") (name "/P8") (class "Default")
      (node (ref "PWM8") (pin "1") (pinfunction "1_1") (pintype "passive"))
      (node (ref "RN3") (pin "5") (pinfunction "5_5") (pintype "passive"))
    )
    (net (code "27") (name "/RST") (class "Default")
      (node (ref "C18") (pin "1") (pinfunction "1_1") (pintype "passive"))
      (node (ref "KEY1") (pin "2") (pinfunction "2_2") (pintype "passive"))
      (node (ref "Q51") (pin "3") (pinfunction "C_3") (pintype "passive"))
      (node (ref "R55") (pin "1") (pinfunction "1_1") (pintype "passive"))
      (node (ref "R63") (pin "2") (pinfunction "2_2") (pintype "passive"))
      (node (ref "T-RST") (pin "1") (pintype "passive"))
      (node (ref "U3") (pin "7") (pinfunction "NRST_7") (pintype "passive"))
    )
    (net (code "28") (name "/SWCLK") (class "Default")
      (node (ref "R28") (pin "1") (pinfunction "1_1") (pintype "passive"))
      (node (ref "U3") (pin "49") (pinfunction "PA14/JTCK/SWCLK_49") (pintype "passive"))
    )
    (net (code "29") (name "/SWDIO") (class "Default")
      (node (ref "R30") (pin "1") (pinfunction "1_1") (pintype "passive"))
      (node (ref "U3") (pin "46") (pinfunction "PA13/JTMS/SWDIO_46") (pintype "passive"))
    )
    (net (code "30") (name "/TIM2_CH1(PA15)") (class "Default")
      (node (ref "RN3") (pin "1") (pinfunction "1_1") (pintype "passive"))
      (node (ref "U3") (pin "50") (pinfunction "PA15/JTDI_50") (pintype "passive"))
    )
    (net (code "31") (name "/TIM2_CH2(PB3)") (class "Default")
      (node (ref "RN3") (pin "2") (pinfunction "2_2") (pintype "passive"))
      (node (ref "U3") (pin "55") (pinfunction "PB3/JTDO/TRACESWO_55") (pintype "passive"))
    )
    (net (code "32") (name "/TIM3_CH1(PB4)") (class "Default")
      (node (ref "RN2") (pin "1") (pinfunction "1_1") (pintype "passive"))
      (node (ref "U3") (pin "56") (pinfunction "PB4/NJRST_56") (pintype "passive"))
    )
    (net (code "33") (name "/TIM3_CH2(PB5)") (class "Default")
      (node (ref "RN2") (pin "2") (pinfunction "2_2") (pintype "passive"))
      (node (ref "U3") (pin "57") (pinfunction "PB5_57") (pintype "passive"))
    )
    (net (code "34") (name "/TIM3_CH3(PB0)") (class "Default")
      (node (ref "RN2") (pin "3") (pinfunction "3_3") (pintype "passive"))
      (node (ref "U3") (pin "26") (pinfunction "PB0_26") (pintype "passive"))
    )
    (net (code "35") (name "/TIM3_CH4(PB1)") (class "Default")
      (node (ref "RN2") (pin "4") (pinfunction "4_4") (pintype "passive"))
      (node (ref "U3") (pin "27") (pinfunction "PB1_27") (pintype "passive"))
    )
    (net (code "36") (name "/TIM8_CH3(PC8)") (class "Default")
      (node (ref "RN3") (pin "4") (pinfunction "4_4") (pintype "passive"))
      (node (ref "U3") (pin "39") (pinfunction "PC8_39") (pintype "passive"))
    )
    (net (code "37") (name "/TIM8_CH4(PC9)") (class "Default")
      (node (ref "RN3") (pin "3") (pinfunction "3_3") (pintype "passive"))
      (node (ref "U3") (pin "40") (pinfunction "PC9_40") (pintype "passive"))
    )
    (net (code "38") (name "/UART4_RX(PA1)") (class "Default")
      (node (ref "R24") (pin "1") (pinfunction "1_1") (pintype "passive"))
      (node (ref "U3") (pin "15") (pinfunction "PA1_15") (pintype "passive"))
    )
    (net (code "39") (name "/UART4_TX(PA0)") (class "Default")
      (node (ref "R25") (pin "1") (pinfunction "1_1") (pintype "passive"))
      (node (ref "U3") (pin "14") (pinfunction "PA0/WKUP_14") (pintype "passive"))
    )
    (net (code "40") (name "/USART1_RX(PA10)") (class "Default")
      (node (ref "R15") (pin "1") (pinfunction "1_1") (pintype "passive"))
      (node (ref "T-USART1_RX") (pin "1") (pintype "passive"))
      (node (ref "U3") (pin "43") (pinfunction "PA10_43") (pintype "passive"))
    )
    (net (code "41") (name "/USART1_TX(PA9)") (class "Default")
      (node (ref "R16") (pin "1") (pinfunction "1_1") (pintype "passive"))
      (node (ref "T-USART1_TX") (pin "1") (pintype "passive"))
      (node (ref "U3") (pin "42") (pinfunction "PA9_42") (pintype "passive"))
    )
    (net (code "42") (name "/USART2_RX(PA3)") (class "Default")
      (node (ref "Q4") (pin "3") (pinfunction "C_3") (pintype "passive"))
      (node (ref "R13") (pin "2") (pinfunction "2_2") (pintype "passive"))
      (node (ref "U3") (pin "17") (pinfunction "PA3_17") (pintype "passive"))
    )
    (net (code "43") (name "/USART3_RX(PB11)") (class "Default")
      (node (ref "R19") (pin "1") (pinfunction "1_1") (pintype "passive"))
      (node (ref "U3") (pin "30") (pinfunction "PB11_30") (pintype "passive"))
    )
    (net (code "44") (name "/USART3_TX(PB10)") (class "Default")
      (node (ref "R22") (pin "1") (pinfunction "1_1") (pintype "passive"))
      (node (ref "U3") (pin "29") (pinfunction "PB10_29") (pintype "passive"))
    )
    (net (code "45") (name "/USART6_RX(PC7)") (class "Default")
      (node (ref "R31") (pin "1") (pinfunction "1_1") (pintype "passive"))
      (node (ref "U3") (pin "38") (pinfunction "PC7_38") (pintype "passive"))
    )
    (net (code "46") (name "/USART6_TX(PC6)") (class "Default")
      (node (ref "R33") (pin "1") (pinfunction "1_1") (pintype "passive"))
      (node (ref "U3") (pin "37") (pinfunction "PC6_37") (pintype "passive"))
    )
    (net (code "47") (name "3.3V") (class "Default")
      (node (ref "C16") (pin "2") (pinfunction "2_2") (pintype "passive"))
      (node (ref "C17") (pin "2") (pinfunction "2_2") (pintype "passive"))
      (node (ref "C23") (pin "1") (pinfunction "1_1") (pintype "passive"))
      (node (ref "C24") (pin "1") (pinfunction "1_1") (pintype "passive"))
      (node (ref "C25") (pin "2") (pinfunction "2_2") (pintype "passive"))
      (node (ref "C31") (pin "1") (pinfunction "1_1") (pintype "passive"))
      (node (ref "CAN1") (pin "3") (pinfunction "VCC_3") (pintype "passive"))
      (node (ref "CAN2") (pin "3") (pinfunction "VCC_3") (pintype "passive"))
      (node (ref "D6") (pin "A") (pinfunction "A_A") (pintype "passive"))
      (node (ref "F2") (pin "1") (pinfunction "1_1") (pintype "passive"))
      (node (ref "J5") (pin "4") (pinfunction "4_4") (pintype "passive"))
      (node (ref "J6") (pin "4") (pinfunction "4_4") (pintype "passive"))
      (node (ref "LED1") (pin "A") (pinfunction "A_A") (pintype "passive"))
      (node (ref "LED2") (pin "A") (pinfunction "A_A") (pintype "passive"))
      (node (ref "R13") (pin "1") (pinfunction "1_1") (pintype "passive"))
      (node (ref "R18") (pin "1") (pinfunction "1_1") (pintype "passive"))
      (node (ref "R42") (pin "1") (pinfunction "1_1") (pintype "passive"))
      (node (ref "R55") (pin "2") (pinfunction "2_2") (pintype "passive"))
      (node (ref "R62") (pin "2") (pinfunction "2_2") (pintype "passive"))
      (node (ref "R63") (pin "1") (pinfunction "1_1") (pintype "passive"))
      (node (ref "U2") (pin "5") (pinfunction "OUT_5") (pintype "passive"))
      (node (ref "U3") (pin "13") (pinfunction "VDDA_13") (pintype "power_in"))
    )
    (net (code "48") (name "3.3V_SWD") (class "Default")
      (node (ref "F2") (pin "2") (pinfunction "2_2") (pintype "passive"))
      (node (ref "J4") (pin "4") (pinfunction "4_4") (pintype "passive"))
    )
    (net (code "49") (name "5V") (class "Default")
      (node (ref "C10") (pin "2") (pinfunction "2_2") (pintype "passive"))
      (node (ref "C11") (pin "2") (pinfunction "2_2") (pintype "passive"))
      (node (ref "C12") (pin "2") (pinfunction "2_2") (pintype "passive"))
      (node (ref "C14") (pin "1") (pinfunction "1_1") (pintype "passive"))
      (node (ref "C15") (pin "1") (pinfunction "1_1") (pintype "passive"))
      (node (ref "C34") (pin "2") (pinfunction "2_2") (pintype "passive"))
      (node (ref "C37") (pin "2") (pinfunction "2_2") (pintype "passive"))
      (node (ref "C41") (pin "2") (pinfunction "2_2") (pintype "passive"))
      (node (ref "C42") (pin "2") (pinfunction "2_2") (pintype "passive"))
      (node (ref "C43") (pin "2") (pinfunction "2_2") (pintype "passive"))
      (node (ref "D7") (pin "1") (pinfunction "C_1") (pintype "passive"))
      (node (ref "DBUS") (pin "2") (pinfunction "2_2") (pintype "passive"))
      (node (ref "F1") (pin "1") (pinfunction "1_1") (pintype "passive"))
      (node (ref "L1") (pin "2") (pinfunction "2_2") (pintype "passive"))
      (node (ref "PWM1") (pin "2") (pinfunction "2_2") (pintype "passive"))
      (node (ref "PWM2") (pin "2") (pinfunction "2_2") (pintype "passive"))
      (node (ref "PWM3") (pin "2") (pinfunction "2_2") (pintype "passive"))
      (node (ref "PWM4") (pin "2") (pinfunction "2_2") (pintype "passive"))
      (node (ref "PWM5") (pin "2") (pinfunction "2_2") (pintype "passive"))
      (node (ref "PWM6") (pin "2") (pinfunction "2_2") (pintype "passive"))
      (node (ref "PWM7") (pin "2") (pinfunction "2_2") (pintype "passive"))
      (node (ref "PWM8") (pin "2") (pinfunction "2_2") (pintype "passive"))
      (node (ref "R9") (pin "1") (pinfunction "1_1") (pintype "passive"))
      (node (ref "U2") (pin "1") (pinfunction "IN_1") (pintype "passive"))
      (node (ref "U2") (pin "3") (pinfunction "EN_3") (pintype "passive"))
    )
    (net (code "50") (name "5V_USART") (class "Default")
      (node (ref "F1") (pin "2") (pinfunction "2_2") (pintype "passive"))
      (node (ref "J10") (pin "4") (pinfunction "4_4") (pintype "passive"))
      (node (ref "J7") (pin "4") (pinfunction "4_4") (pintype "passive"))
      (node (ref "J8") (pin "4") (pinfunction "4_4") (pintype "passive"))
      (node (ref "J9") (pin "4") (pinfunction "4_4") (pintype "passive"))
    )
    (net (code "51") (name "24V") (class "Default")
      (node (ref "J1") (pin "1") (pinfunction "VCC_1") (pintype "passive"))
      (node (ref "J2") (pin "1") (pinfunction "VCC_1") (pintype "passive"))
      (node (ref "J3") (pin "1") (pinfunction "VCC_1") (pintype "passive"))
      (node (ref "P5") (pin "4") (pinfunction "VCC_4") (pintype "passive"))
      (node (ref "P5") (pin "5") (pinfunction "VCC_5") (pintype "passive"))
      (node (ref "P5") (pin "6") (pinfunction "VCC_6") (pintype "passive"))
      (node (ref "P6") (pin "4") (pinfunction "VCC_4") (pintype "passive"))
      (node (ref "P6") (pin "5") (pinfunction "VCC_5") (pintype "passive"))
      (node (ref "P6") (pin "6") (pinfunction "VCC_6") (pintype "passive"))
      (node (ref "Q1 PMOS") (pin "1") (pinfunction "S_1") (pintype "passive"))
      (node (ref "Q1 PMOS") (pin "2") (pinfunction "S_2") (pintype "passive"))
      (node (ref "Q1 PMOS") (pin "3") (pinfunction "S_3") (pintype "passive"))
      (node (ref "Q2") (pin "1") (pinfunction "E_1") (pintype "passive"))
      (node (ref "R2") (pin "2") (pinfunction "2_2") (pintype "passive"))
      (node (ref "R3") (pin "2") (pinfunction "2_2") (pintype "passive"))
      (node (ref "R50") (pin "2") (pinfunction "2_2") (pintype "passive"))
    )
    (net (code "52") (name "24V_OUT") (class "Default")
      (node (ref "3.3A") (pin "1") (pinfunction "1_1") (pintype "passive"))
      (node (ref "C1") (pin "2") (pinfunction "2_2") (pintype "passive"))
      (node (ref "C2") (pin "2") (pinfunction "2_2") (pintype "passive"))
      (node (ref "C3") (pin "1") (pinfunction "1_1") (pintype "passive"))
      (node (ref "C38") (pin "2") (pinfunction "2_2") (pintype "passive"))
      (node (ref "C39") (pin "2") (pinfunction "2_2") (pintype "passive"))
      (node (ref "C4") (pin "1") (pinfunction "1_1") (pintype "passive"))
      (node (ref "C5") (pin "1") (pinfunction "1_1") (pintype "passive"))
      (node (ref "D1") (pin "2") (pinfunction "2_2") (pintype "passive"))
      (node (ref "R8") (pin "2") (pinfunction "2_2") (pintype "passive"))
      (node (ref "U1") (pin "5") (pinfunction "VIN_5") (pintype "passive"))
    )
    (net (code "53") (name "AGND") (class "Default")
      (node (ref "C24") (pin "2") (pinfunction "2_2") (pintype "passive"))
      (node (ref "C25") (pin "1") (pinfunction "1_1") (pintype "passive"))
      (node (ref "R46") (pin "1") (pinfunction "1_1") (pintype "passive"))
      (node (ref "U3") (pin "12") (pinfunction "VSSA_12") (pintype "power_in"))
    )
    (net (code "54") (name "GND") (class "Default")
      (node (ref "C18") (pin "2") (pinfunction "2_2") (pintype "passive"))
      (node (ref "C19") (pin "2") (pinfunction "2_2") (pintype "passive"))
      (node (ref "C20") (pin "1") (pinfunction "1_1") (pintype "passive"))
      (node (ref "C21") (pin "1") (pinfunction "1_1") (pintype "passive"))
      (node (ref "C22") (pin "1") (pinfunction "1_1") (pintype "passive"))
      (node (ref "C23") (pin "2") (pinfunction "2_2") (pintype "passive"))
      (node (ref "C26") (pin "2") (pinfunction "2_2") (pintype "passive"))
      (node (ref "C27") (pin "1") (pinfunction "1_1") (pintype "passive"))
      (node (ref "C28") (pin "1") (pinfunction "1_1") (pintype "passive"))
      (node (ref "C29") (pin "2") (pinfunction "2_2") (pintype "passive"))
      (node (ref "C30") (pin "2") (pinfunction "2_2") (pintype "passive"))
      (node (ref "C31") (pin "2") (pinfunction "2_2") (pintype "passive"))
      (node (ref "C32") (pin "1") (pinfunction "1_1") (pintype "passive"))
      (node (ref "C33") (pin "1") (pinfunction "1_1") (pintype "passive"))
      (node (ref "C50") (pin "1") (pinfunction "1_1") (pintype "passive"))
      (node (ref "C51") (pin "1") (pinfunction "1_1") (pintype "passive"))
      (node (ref "CAN1") (pin "2") (pinfunction "GND_2") (pintype "passive"))
      (node (ref "CAN1") (pin "8") (pinfunction "RS_8") (pintype "passive"))
      (node (ref "CAN2") (pin "2") (pinfunction "GND_2") (pintype "passive"))
      (node (ref "CAN2") (pin "8") (pinfunction "RS_8") (pintype "passive"))
      (node (ref "D7") (pin "2") (pinfunction "A_2") (pintype "passive"))
      (node (ref "J10") (pin "3") (pinfunction "3_3") (pintype "passive"))
      (node (ref "J10") (pin "5") (pinfunction "5_5") (pintype "passive"))
      (node (ref "J10") (pin "6") (pinfunction "6_6") (pintype "passive"))
      (node (ref "J4") (pin "3") (pinfunction "3_3") (pintype "passive"))
      (node (ref "J4") (pin "5") (pinfunction "5_5") (pintype "passive"))
      (node (ref "J4") (pin "6") (pinfunction "6_6") (pintype "passive"))
      (node (ref "J5") (pin "3") (pinfunction "3_3") (pintype "passive"))
      (node (ref "J5") (pin "5") (pinfunction "5_5") (pintype "passive"))
      (node (ref "J5") (pin "6") (pinfunction "6_6") (pintype "passive"))
      (node (ref "J6") (pin "3") (pinfunction "3_3") (pintype "passive"))
      (node (ref "J6") (pin "5") (pinfunction "5_5") (pintype "passive"))
      (node (ref "J6") (pin "6") (pinfunction "6_6") (pintype "passive"))
      (node (ref "J7") (pin "3") (pinfunction "3_3") (pintype "passive"))
      (node (ref "J7") (pin "5") (pinfunction "5_5") (pintype "passive"))
      (node (ref "J7") (pin "6") (pinfunction "6_6") (pintype "passive"))
      (node (ref "J8") (pin "3") (pinfunction "3_3") (pintype "passive"))
      (node (ref "J8") (pin "5") (pinfunction "5_5") (pintype "passive"))
      (node (ref "J8") (pin "6") (pinfunction "6_6") (pintype "passive"))
      (node (ref "J9") (pin "3") (pinfunction "3_3") (pintype "passive"))
      (node (ref "J9") (pin "5") (pinfunction "5_5") (pintype "passive"))
      (node (ref "J9") (pin "6") (pinfunction "6_6") (pintype "passive"))
      (node (ref "KEY1") (pin "1") (pinfunction "1_1") (pintype "passive"))
      (node (ref "Q50") (pin "1") (pinfunction "E_1") (pintype "passive"))
      (node (ref "Q51") (pin "1") (pinfunction "E_1") (pintype "passive"))
      (node (ref "R23") (pin "1") (pinfunction "1_1") (pintype "passive"))
      (node (ref "R41") (pin "2") (pinfunction "2_2") (pintype "passive"))
      (node (ref "R44") (pin "2") (pinfunction "2_2") (pintype "passive"))
      (node (ref "R45") (pin "1") (pinfunction "1_1") (pintype "passive"))
      (node (ref "R47") (pin "1") (pinfunction "1_1") (pintype "passive"))
      (node (ref "R61") (pin "1") (pinfunction "1_1") (pintype "passive"))
      (node (ref "R64") (pin "1") (pinfunction "1_1") (pintype "passive"))
      (node (ref "T-GND1") (pin "1") (pintype "passive"))
      (node (ref "T-GND2") (pin "1") (pintype "passive"))
      (node (ref "T-GND3") (pin "1") (pintype "passive"))
      (node (ref "U3") (pin "18") (pinfunction "VSS_18") (pintype "power_in"))
      (node (ref "U3") (pin "63") (pinfunction "VSS_63") (pintype "power_in"))
    )
    (net (code "55") (name "IGND") (class "Default")
      (node (ref "C7") (pin "1") (pinfunction "1_1") (pintype "passive"))
      (node (ref "D2") (pin "2") (pinfunction "A_2") (pintype "passive"))
      (node (ref "J1") (pin "2") (pinfunction "GND_2") (pintype "passive"))
      (node (ref "J2") (pin "2") (pinfunction "GND_2") (pintype "passive"))
      (node (ref "J3") (pin "2") (pinfunction "GND_2") (pintype "passive"))
      (node (ref "P5") (pin "1") (pinfunction "GND_1") (pintype "passive"))
      (node (ref "P5") (pin "10") (pinfunction "GND_10") (pintype "passive"))
      (node (ref "P5") (pin "2") (pinfunction "GND_2") (pintype "passive"))
      (node (ref "P5") (pin "3") (pinfunction "GND_3") (pintype "passive"))
      (node (ref "P5") (pin "9") (pinfunction "GND_9") (pintype "passive"))
      (node (ref "P6") (pin "1") (pinfunction "GND_1") (pintype "passive"))
      (node (ref "P6") (pin "10") (pinfunction "GND_10") (pintype "passive"))
      (node (ref "P6") (pin "2") (pinfunction "GND_2") (pintype "passive"))
      (node (ref "P6") (pin "3") (pinfunction "GND_3") (pintype "passive"))
      (node (ref "P6") (pin "9") (pinfunction "GND_9") (pintype "passive"))
      (node (ref "Q3 NMOS") (pin "5") (pinfunction "D_5") (pintype "passive"))
      (node (ref "Q3 NMOS") (pin "6") (pinfunction "D_6") (pintype "passive"))
      (node (ref "Q3 NMOS") (pin "7") (pinfunction "D_7") (pintype "passive"))
      (node (ref "Q3 NMOS") (pin "8") (pinfunction "D_8") (pintype "passive"))
    )
    (net (code "56") (name "Net-(C6-Pad2)") (class "Default")
      (node (ref "C6") (pin "2") (pinfunction "2_2") (pintype "passive"))
      (node (ref "R51") (pin "1") (pinfunction "1_1") (pintype "passive"))
    )
    (net (code "57") (name "Net-(C7-Pad2)") (class "Default")
      (node (ref "C7") (pin "2") (pinfunction "2_2") (pintype "passive"))
      (node (ref "R50") (pin "1") (pinfunction "1_1") (pintype "passive"))
    )
    (net (code "58") (name "Net-(C27-Pad2)") (class "Default")
      (node (ref "C27") (pin "2") (pinfunction "2_2") (pintype "passive"))
      (node (ref "R18") (pin "2") (pinfunction "2_2") (pintype "passive"))
      (node (ref "R21") (pin "1") (pinfunction "1_1") (pintype "passive"))
      (node (ref "R23") (pin "2") (pinfunction "2_2") (pintype "passive"))
    )
    (net (code "59") (name "Net-(D2-K)") (class "Default")
      (node (ref "D2") (pin "1") (pinfunction "K_1") (pintype "passive"))
      (node (ref "R3") (pin "1") (pinfunction "1_1") (pintype "passive"))
      (node (ref "R4") (pin "1") (pinfunction "1_1") (pintype "passive"))
    )
    (net (code "60") (name "Net-(D3-A)") (class "Default")
      (node (ref "D3") (pin "2") (pinfunction "A_2") (pintype "passive"))
      (node (ref "Q1 PMOS") (pin "4") (pinfunction "G_4") (pintype "passive"))
      (node (ref "R5") (pin "2") (pinfunction "2_2") (pintype "passive"))
    )
    (net (code "61") (name "Net-(D3-C)") (class "Default")
      (node (ref "3.3A") (pin "2") (pinfunction "2_2") (pintype "passive"))
      (node (ref "D3") (pin "1") (pinfunction "C_1") (pintype "passive"))
      (node (ref "Q1 PMOS") (pin "5") (pinfunction "D_5") (pintype "passive"))
      (node (ref "Q1 PMOS") (pin "6") (pinfunction "D_6") (pintype "passive"))
      (node (ref "Q1 PMOS") (pin "7") (pinfunction "D_7") (pintype "passive"))
      (node (ref "Q1 PMOS") (pin "8") (pinfunction "D_8") (pintype "passive"))
      (node (ref "R1") (pin "2") (pinfunction "2_2") (pintype "passive"))
      (node (ref "R51") (pin "2") (pinfunction "2_2") (pintype "passive"))
    )
    (net (code "62") (name "Net-(D4-C)") (class "Default")
      (node (ref "D4") (pin "1") (pinfunction "C_1") (pintype "passive"))
      (node (ref "Q3 NMOS") (pin "4") (pinfunction "G_4") (pintype "passive"))
      (node (ref "R2") (pin "1") (pinfunction "1_1") (pintype "passive"))
    )
    (net (code "63") (name "Net-(D5-K)") (class "Default")
      (node (ref "C9") (pin "1") (pinfunction "1_1") (pintype "passive"))
      (node (ref "D5") (pin "1") (pinfunction "K_1") (pintype "passive"))
      (node (ref "L1") (pin "1") (pinfunction "1_1") (pintype "passive"))
      (node (ref "U1") (pin "6") (pinfunction "SW_6") (pintype "passive"))
    )
    (net (code "64") (name "Net-(D6-PadK)") (class "Default")
      (node (ref "D6") (pin "K") (pinfunction "K_K") (pintype "passive"))
      (node (ref "R41") (pin "1") (pinfunction "1_1") (pintype "passive"))
    )
    (net (code "65") (name "Net-(D50-K)") (class "Default")
      (node (ref "D50") (pin "1") (pinfunction "K_1") (pintype "passive"))
      (node (ref "R60") (pin "1") (pinfunction "1_1") (pintype "passive"))
    )
    (net (code "66") (name "Net-(GPIO1-Pad1)") (class "Default")
      (node (ref "GPIO1") (pin "1") (pinfunction "1_1") (pintype "passive"))
      (node (ref "RN1") (pin "1") (pinfunction "1_1") (pintype "passive"))
    )
    (net (code "67") (name "Net-(GPIO1-Pad2)") (class "Default")
      (node (ref "GPIO1") (pin "2") (pinfunction "2_2") (pintype "passive"))
      (node (ref "RN1") (pin "2") (pinfunction "2_2") (pintype "passive"))
    )
    (net (code "68") (name "Net-(GPIO1-Pad3)") (class "Default")
      (node (ref "GPIO1") (pin "3") (pinfunction "3_3") (pintype "passive"))
      (node (ref "RN1") (pin "3") (pinfunction "3_3") (pintype "passive"))
    )
    (net (code "69") (name "Net-(GPIO1-Pad4)") (class "Default")
      (node (ref "GPIO1") (pin "4") (pinfunction "4_4") (pintype "passive"))
      (node (ref "RN1") (pin "4") (pinfunction "4_4") (pintype "passive"))
    )
    (net (code "70") (name "Net-(GPIO1-Pad5)") (class "Default")
      (node (ref "GPIO1") (pin "5") (pinfunction "5_5") (pintype "passive"))
      (node (ref "R36") (pin "2") (pinfunction "2_2") (pintype "passive"))
    )
    (net (code "71") (name "Net-(GPIO1-Pad6)") (class "Default")
      (node (ref "GPIO1") (pin "6") (pinfunction "6_6") (pintype "passive"))
      (node (ref "R38") (pin "2") (pinfunction "2_2") (pintype "passive"))
    )
    (net (code "72") (name "Net-(J4-Pad1)") (class "Default")
      (node (ref "J4") (pin "1") (pinfunction "1_1") (pintype "passive"))
      (node (ref "R30") (pin "2") (pinfunction "2_2") (pintype "passive"))
    )
    (net (code "73") (name "Net-(J4-Pad2)") (class "Default")
      (node (ref "J4") (pin "2") (pinfunction "2_2") (pintype "passive"))
      (node (ref "R28") (pin "2") (pinfunction "2_2") (pintype "passive"))
    )
    (net (code "74") (name "Net-(J7-Pad1)") (class "Default")
      (node (ref "J7") (pin "1") (pinfunction "1_1") (pintype "passive"))
      (node (ref "R16") (pin "2") (pinfunction "2_2") (pintype "passive"))
    )
    (net (code "75") (name "Net-(J7-Pad2)") (class "Default")
      (node (ref "J7") (pin "2") (pinfunction "2_2") (pintype "passive"))
      (node (ref "R15") (pin "2") (pinfunction "2_2") (pintype "passive"))
    )
    (net (code "76") (name "Net-(J8-Pad1)") (class "Default")
      (node (ref "J8") (pin "1") (pinfunction "1_1") (pintype "passive"))
      (node (ref "R22") (pin "2") (pinfunction "2_2") (pintype "passive"))
    )
    (net (code "77") (name "Net-(J8-Pad2)") (class "Default")
      (node (ref "J8") (pin "2") (pinfunction "2_2") (pintype "passive"))
      (node (ref "R19") (pin "2") (pinfunction "2_2") (pintype "passive"))
    )
    (net (code "78") (name "Net-(J9-Pad1)") (class "Default")
      (node (ref "J9") (pin "1") (pinfunction "1_1") (pintype "passive"))
      (node (ref "R25") (pin "2") (pinfunction "2_2") (pintype "passive"))
    )
    (net (code "79") (name "Net-(J9-Pad2)") (class "Default")
      (node (ref "J9") (pin "2") (pinfunction "2_2") (pintype "passive"))
      (node (ref "R24") (pin "2") (pinfunction "2_2") (pintype "passive"))
    )
    (net (code "80") (name "Net-(J10-Pad1)") (class "Default")
      (node (ref "J10") (pin "1") (pinfunction "1_1") (pintype "passive"))
      (node (ref "R33") (pin "2") (pinfunction "2_2") (pintype "passive"))
    )
    (net (code "81") (name "Net-(J10-Pad2)") (class "Default")
      (node (ref "J10") (pin "2") (pinfunction "2_2") (pintype "passive"))
      (node (ref "R31") (pin "2") (pinfunction "2_2") (pintype "passive"))
    )
    (net (code "82") (name "Net-(LED1-PadK)") (class "Default")
      (node (ref "LED1") (pin "K") (pinfunction "K_K") (pintype "passive"))
      (node (ref "R54") (pin "1") (pinfunction "1_1") (pintype "passive"))
    )
    (net (code "83") (name "Net-(LED2-PadK)") (class "Default")
      (node (ref "LED2") (pin "K") (pinfunction "K_K") (pintype "passive"))
      (node (ref "R53") (pin "1") (pinfunction "1_1") (pintype "passive"))
    )
    (net (code "84") (name "Net-(Q2-B)") (class "Default")
      (node (ref "C8") (pin "2") (pinfunction "2_2") (pintype "passive"))
      (node (ref "Q2") (pin "2") (pinfunction "B_2") (pintype "passive"))
      (node (ref "R1") (pin "1") (pinfunction "1_1") (pintype "passive"))
      (node (ref "R4") (pin "2") (pinfunction "2_2") (pintype "passive"))
    )
    (net (code "85") (name "Net-(Q2-C)") (class "Default")
      (node (ref "C8") (pin "1") (pinfunction "1_1") (pintype "passive"))
      (node (ref "Q2") (pin "3") (pinfunction "C_3") (pintype "passive"))
      (node (ref "R5") (pin "1") (pinfunction "1_1") (pintype "passive"))
      (node (ref "R6") (pin "2") (pinfunction "2_2") (pintype "passive"))
    )
    (net (code "86") (name "Net-(Q4-B)") (class "Default")
      (node (ref "Q4") (pin "2") (pinfunction "B_2") (pintype "passive"))
      (node (ref "R14") (pin "1") (pinfunction "1_1") (pintype "passive"))
    )
    (net (code "87") (name "Net-(Q50-B)") (class "Default")
      (node (ref "C50") (pin "2") (pinfunction "2_2") (pintype "passive"))
      (node (ref "Q50") (pin "2") (pinfunction "B_2") (pintype "passive"))
      (node (ref "R60") (pin "2") (pinfunction "2_2") (pintype "passive"))
      (node (ref "R61") (pin "2") (pinfunction "2_2") (pintype "passive"))
    )
    (net (code "88") (name "Net-(Q50-C)") (class "Default")
      (node (ref "C51") (pin "2") (pinfunction "2_2") (pintype "passive"))
      (node (ref "Q50") (pin "3") (pinfunction "C_3") (pintype "passive"))
      (node (ref "Q51") (pin "2") (pinfunction "B_2") (pintype "passive"))
      (node (ref "R62") (pin "1") (pinfunction "1_1") (pintype "passive"))
      (node (ref "R64") (pin "2") (pinfunction "2_2") (pintype "passive"))
    )
    (net (code "89") (name "Net-(U1-BST)") (class "Default")
      (node (ref "C9") (pin "2") (pinfunction "2_2") (pintype "passive"))
      (node (ref "U1") (pin "1") (pinfunction "BST_1") (pintype "passive"))
    )
    (net (code "90") (name "Net-(U1-EN)") (class "Default")
      (node (ref "R8") (pin "1") (pinfunction "1_1") (pintype "passive"))
      (node (ref "U1") (pin "4") (pinfunction "EN_4") (pintype "passive"))
    )
    (net (code "91") (name "Net-(U1-FB)") (class "Default")
      (node (ref "C14") (pin "2") (pinfunction "2_2") (pintype "passive"))
      (node (ref "R7") (pin "2") (pinfunction "2_2") (pintype "passive"))
      (node (ref "R9") (pin "2") (pinfunction "2_2") (pintype "passive"))
      (node (ref "U1") (pin "3") (pinfunction "FB_3") (pintype "passive"))
    )
    (net (code "92") (name "Net-(U2-BYT)") (class "Default")
      (node (ref "C40") (pin "1") (pinfunction "1_1") (pintype "passive"))
      (node (ref "U2") (pin "4") (pinfunction "BYT_4") (pintype "passive"))
    )
    (net (code "93") (name "Net-(U3-BOOT0)") (class "Default")
      (node (ref "R44") (pin "1") (pinfunction "1_1") (pintype "passive"))
      (node (ref "T-BOOT0") (pin "1") (pintype "passive"))
      (node (ref "U3") (pin "60") (pinfunction "BOOT0_60") (pintype "passive"))
    )
    (net (code "94") (name "Net-(U3-PB2{slash}BOOT1)") (class "Default")
      (node (ref "R45") (pin "2") (pinfunction "2_2") (pintype "passive"))
      (node (ref "T-BOOT1") (pin "1") (pintype "passive"))
      (node (ref "U3") (pin "28") (pinfunction "PB2/BOOT1_28") (pintype "passive"))
    )
    (net (code "95") (name "Net-(U3-PH0{slash}OSC_IN)") (class "Default")
      (node (ref "C21") (pin "2") (pinfunction "2_2") (pintype "passive"))
      (node (ref "U3") (pin "5") (pinfunction "PH0/OSC_IN_5") (pintype "passive"))
      (node (ref "Y1") (pin "3") (pinfunction "OSC2_3") (pintype "passive"))
    )
    (net (code "96") (name "Net-(U3-PH1{slash}OSC_OUT)") (class "Default")
      (node (ref "C22") (pin "2") (pinfunction "2_2") (pintype "passive"))
      (node (ref "U3") (pin "6") (pinfunction "PH1/OSC_OUT_6") (pintype "passive"))
      (node (ref "Y1") (pin "1") (pinfunction "OSC1_1") (pintype "passive"))
    )
    (net (code "97") (name "Net-(U3-VCAP_1)") (class "Default")
      (node (ref "C32") (pin "2") (pinfunction "2_2") (pintype "passive"))
      (node (ref "U3") (pin "31") (pinfunction "VCAP_1_31") (pintype "passive"))
    )
    (net (code "98") (name "Net-(U3-VCAP_2)") (class "Default")
      (node (ref "C30") (pin "1") (pinfunction "1_1") (pintype "passive"))
      (node (ref "U3") (pin "47") (pinfunction "VCAP_2_47") (pintype "passive"))
    )
    (net (code "99") (name "PGND") (class "Default")
      (node (ref "C1") (pin "1") (pinfunction "1_1") (pintype "passive"))
      (node (ref "C10") (pin "1") (pinfunction "1_1") (pintype "passive"))
      (node (ref "C11") (pin "1") (pinfunction "1_1") (pintype "passive"))
      (node (ref "C12") (pin "1") (pinfunction "1_1") (pintype "passive"))
      (node (ref "C15") (pin "2") (pinfunction "2_2") (pintype "passive"))
      (node (ref "C16") (pin "1") (pinfunction "1_1") (pintype "passive"))
      (node (ref "C17") (pin "1") (pinfunction "1_1") (pintype "passive"))
      (node (ref "C2") (pin "1") (pinfunction "1_1") (pintype "passive"))
      (node (ref "C3") (pin "2") (pinfunction "2_2") (pintype "passive"))
      (node (ref "C34") (pin "1") (pinfunction "1_1") (pintype "passive"))
      (node (ref "C37") (pin "1") (pinfunction "1_1") (pintype "passive"))
      (node (ref "C38") (pin "1") (pinfunction "1_1") (pintype "passive"))
      (node (ref "C39") (pin "1") (pinfunction "1_1") (pintype "passive"))
      (node (ref "C4") (pin "2") (pinfunction "2_2") (pintype "passive"))
      (node (ref "C40") (pin "2") (pinfunction "2_2") (pintype "passive"))
      (node (ref "C41") (pin "1") (pinfunction "1_1") (pintype "passive"))
      (node (ref "C42") (pin "1") (pinfunction "1_1") (pintype "passive"))
      (node (ref "C43") (pin "1") (pinfunction "1_1") (pintype "passive"))
      (node (ref "C5") (pin "2") (pinfunction "2_2") (pintype "passive"))
      (node (ref "C6") (pin "1") (pinfunction "1_1") (pintype "passive"))
      (node (ref "D1") (pin "1") (pinfunction "1_1") (pintype "passive"))
      (node (ref "D4") (pin "2") (pinfunction "A_2") (pintype "passive"))
      (node (ref "D5") (pin "2") (pinfunction "A_2") (pintype "passive"))
      (node (ref "DBUS") (pin "1") (pinfunction "1_1") (pintype "passive"))
      (node (ref "PWM1") (pin "3") (pinfunction "3_3") (pintype "passive"))
      (node (ref "PWM2") (pin "3") (pinfunction "3_3") (pintype "passive"))
      (node (ref "PWM3") (pin "3") (pinfunction "3_3") (pintype "passive"))
      (node (ref "PWM4") (pin "3") (pinfunction "3_3") (pintype "passive"))
      (node (ref "PWM5") (pin "3") (pinfunction "3_3") (pintype "passive"))
      (node (ref "PWM6") (pin "3") (pinfunction "3_3") (pintype "passive"))
      (node (ref "PWM7") (pin "3") (pinfunction "3_3") (pintype "passive"))
      (node (ref "PWM8") (pin "3") (pinfunction "3_3") (pintype "passive"))
      (node (ref "Q3 NMOS") (pin "1") (pinfunction "S_1") (pintype "passive"))
      (node (ref "Q3 NMOS") (pin "2") (pinfunction "S_2") (pintype "passive"))
      (node (ref "Q3 NMOS") (pin "3") (pinfunction "S_3") (pintype "passive"))
      (node (ref "Q4") (pin "1") (pinfunction "E_1") (pintype "passive"))
      (node (ref "R46") (pin "2") (pinfunction "2_2") (pintype "passive"))
      (node (ref "R47") (pin "2") (pinfunction "2_2") (pintype "passive"))
      (node (ref "R6") (pin "1") (pinfunction "1_1") (pintype "passive"))
      (node (ref "R7") (pin "1") (pinfunction "1_1") (pintype "passive"))
      (node (ref "U1") (pin "2") (pinfunction "GND_2") (pintype "passive"))
      (node (ref "U2") (pin "2") (pinfunction "GND_2") (pintype "passive"))
    )
    (net (code "100") (name "VDD") (class "Default")
      (node (ref "C19") (pin "1") (pinfunction "1_1") (pintype "passive"))
      (node (ref "C20") (pin "2") (pinfunction "2_2") (pintype "passive"))
      (node (ref "C26") (pin "1") (pinfunction "1_1") (pintype "passive"))
      (node (ref "C28") (pin "2") (pinfunction "2_2") (pintype "passive"))
      (node (ref "C29") (pin "1") (pinfunction "1_1") (pintype "passive"))
      (node (ref "C33") (pin "2") (pinfunction "2_2") (pintype "passive"))
      (node (ref "R42") (pin "2") (pinfunction "2_2") (pintype "passive"))
      (node (ref "T-1") (pin "1") (pintype "passive"))
      (node (ref "U3") (pin "1") (pinfunction "VBAT_1") (pintype "power_in"))
      (node (ref "U3") (pin "19") (pinfunction "VDD_19") (pintype "power_in"))
      (node (ref "U3") (pin "32") (pinfunction "VDD_32") (pintype "power_in"))
      (node (ref "U3") (pin "48") (pinfunction "VDD_48") (pintype "power_in"))
      (node (ref "U3") (pin "64") (pinfunction "VDD_64") (pintype "power_in"))
    )
    (net (code "101") (name "unconnected-(CAN1-LBK-Pad5)") (class "Default")
      (node (ref "CAN1") (pin "5") (pinfunction "LBK_5") (pintype "passive+no_connect"))
    )
    (net (code "102") (name "unconnected-(CAN2-LBK-Pad5)") (class "Default")
      (node (ref "CAN2") (pin "5") (pinfunction "LBK_5") (pintype "passive+no_connect"))
    )
    (net (code "103") (name "unconnected-(U3-PA2-Pad16)") (class "Default")
      (node (ref "U3") (pin "16") (pinfunction "PA2_16") (pintype "passive"))
    )
    (net (code "104") (name "unconnected-(U3-PA8-Pad41)") (class "Default")
      (node (ref "U3") (pin "41") (pinfunction "PA8_41") (pintype "passive"))
    )
    (net (code "105") (name "unconnected-(U3-PB6-Pad58)") (class "Default")
      (node (ref "U3") (pin "58") (pinfunction "PB6_58") (pintype "passive"))
    )
    (net (code "106") (name "unconnected-(U3-PB7-Pad59)") (class "Default")
      (node (ref "U3") (pin "59") (pinfunction "PB7_59") (pintype "passive"))
    )
    (net (code "107") (name "unconnected-(U3-PB8-Pad61)") (class "Default")
      (node (ref "U3") (pin "61") (pinfunction "PB8_61") (pintype "passive"))
    )
    (net (code "108") (name "unconnected-(U3-PB9-Pad62)") (class "Default")
      (node (ref "U3") (pin "62") (pinfunction "PB9_62") (pintype "passive"))
    )
    (net (code "109") (name "unconnected-(U3-PB14-Pad35)") (class "Default")
      (node (ref "U3") (pin "35") (pinfunction "PB14_35") (pintype "passive"))
    )
    (net (code "110") (name "unconnected-(U3-PB15-Pad36)") (class "Default")
      (node (ref "U3") (pin "36") (pinfunction "PB15_36") (pintype "passive"))
    )
    (net (code "111") (name "unconnected-(U3-PC0-Pad8)") (class "Default")
      (node (ref "U3") (pin "8") (pinfunction "PC0_8") (pintype "passive"))
    )
    (net (code "112") (name "unconnected-(U3-PC2-Pad10)") (class "Default")
      (node (ref "U3") (pin "10") (pinfunction "PC2_10") (pintype "passive"))
    )
    (net (code "113") (name "unconnected-(U3-PC3-Pad11)") (class "Default")
      (node (ref "U3") (pin "11") (pinfunction "PC3_11") (pintype "passive"))
    )
    (net (code "114") (name "unconnected-(U3-PC10-Pad51)") (class "Default")
      (node (ref "U3") (pin "51") (pinfunction "PC10_51") (pintype "passive"))
    )
    (net (code "115") (name "unconnected-(U3-PC11-Pad52)") (class "Default")
      (node (ref "U3") (pin "52") (pinfunction "PC11_52") (pintype "passive"))
    )
    (net (code "116") (name "unconnected-(U3-PC12-Pad53)") (class "Default")
      (node (ref "U3") (pin "53") (pinfunction "PC12_53") (pintype "passive"))
    )
    (net (code "117") (name "unconnected-(U3-PC15{slash}OSC32_OUT-Pad4)") (class "Default")
      (node (ref "U3") (pin "4") (pinfunction "PC15/OSC32_OUT_4") (pintype "passive"))
    )
    (net (code "118") (name "unconnected-(U3-PD2-Pad54)") (class "Default")
      (node (ref "U3") (pin "54") (pinfunction "PD2_54") (pintype "passive"))
    )
  )
)
